# tfmsx.net
KiCad netlist of a schematic drawn in EAGLE
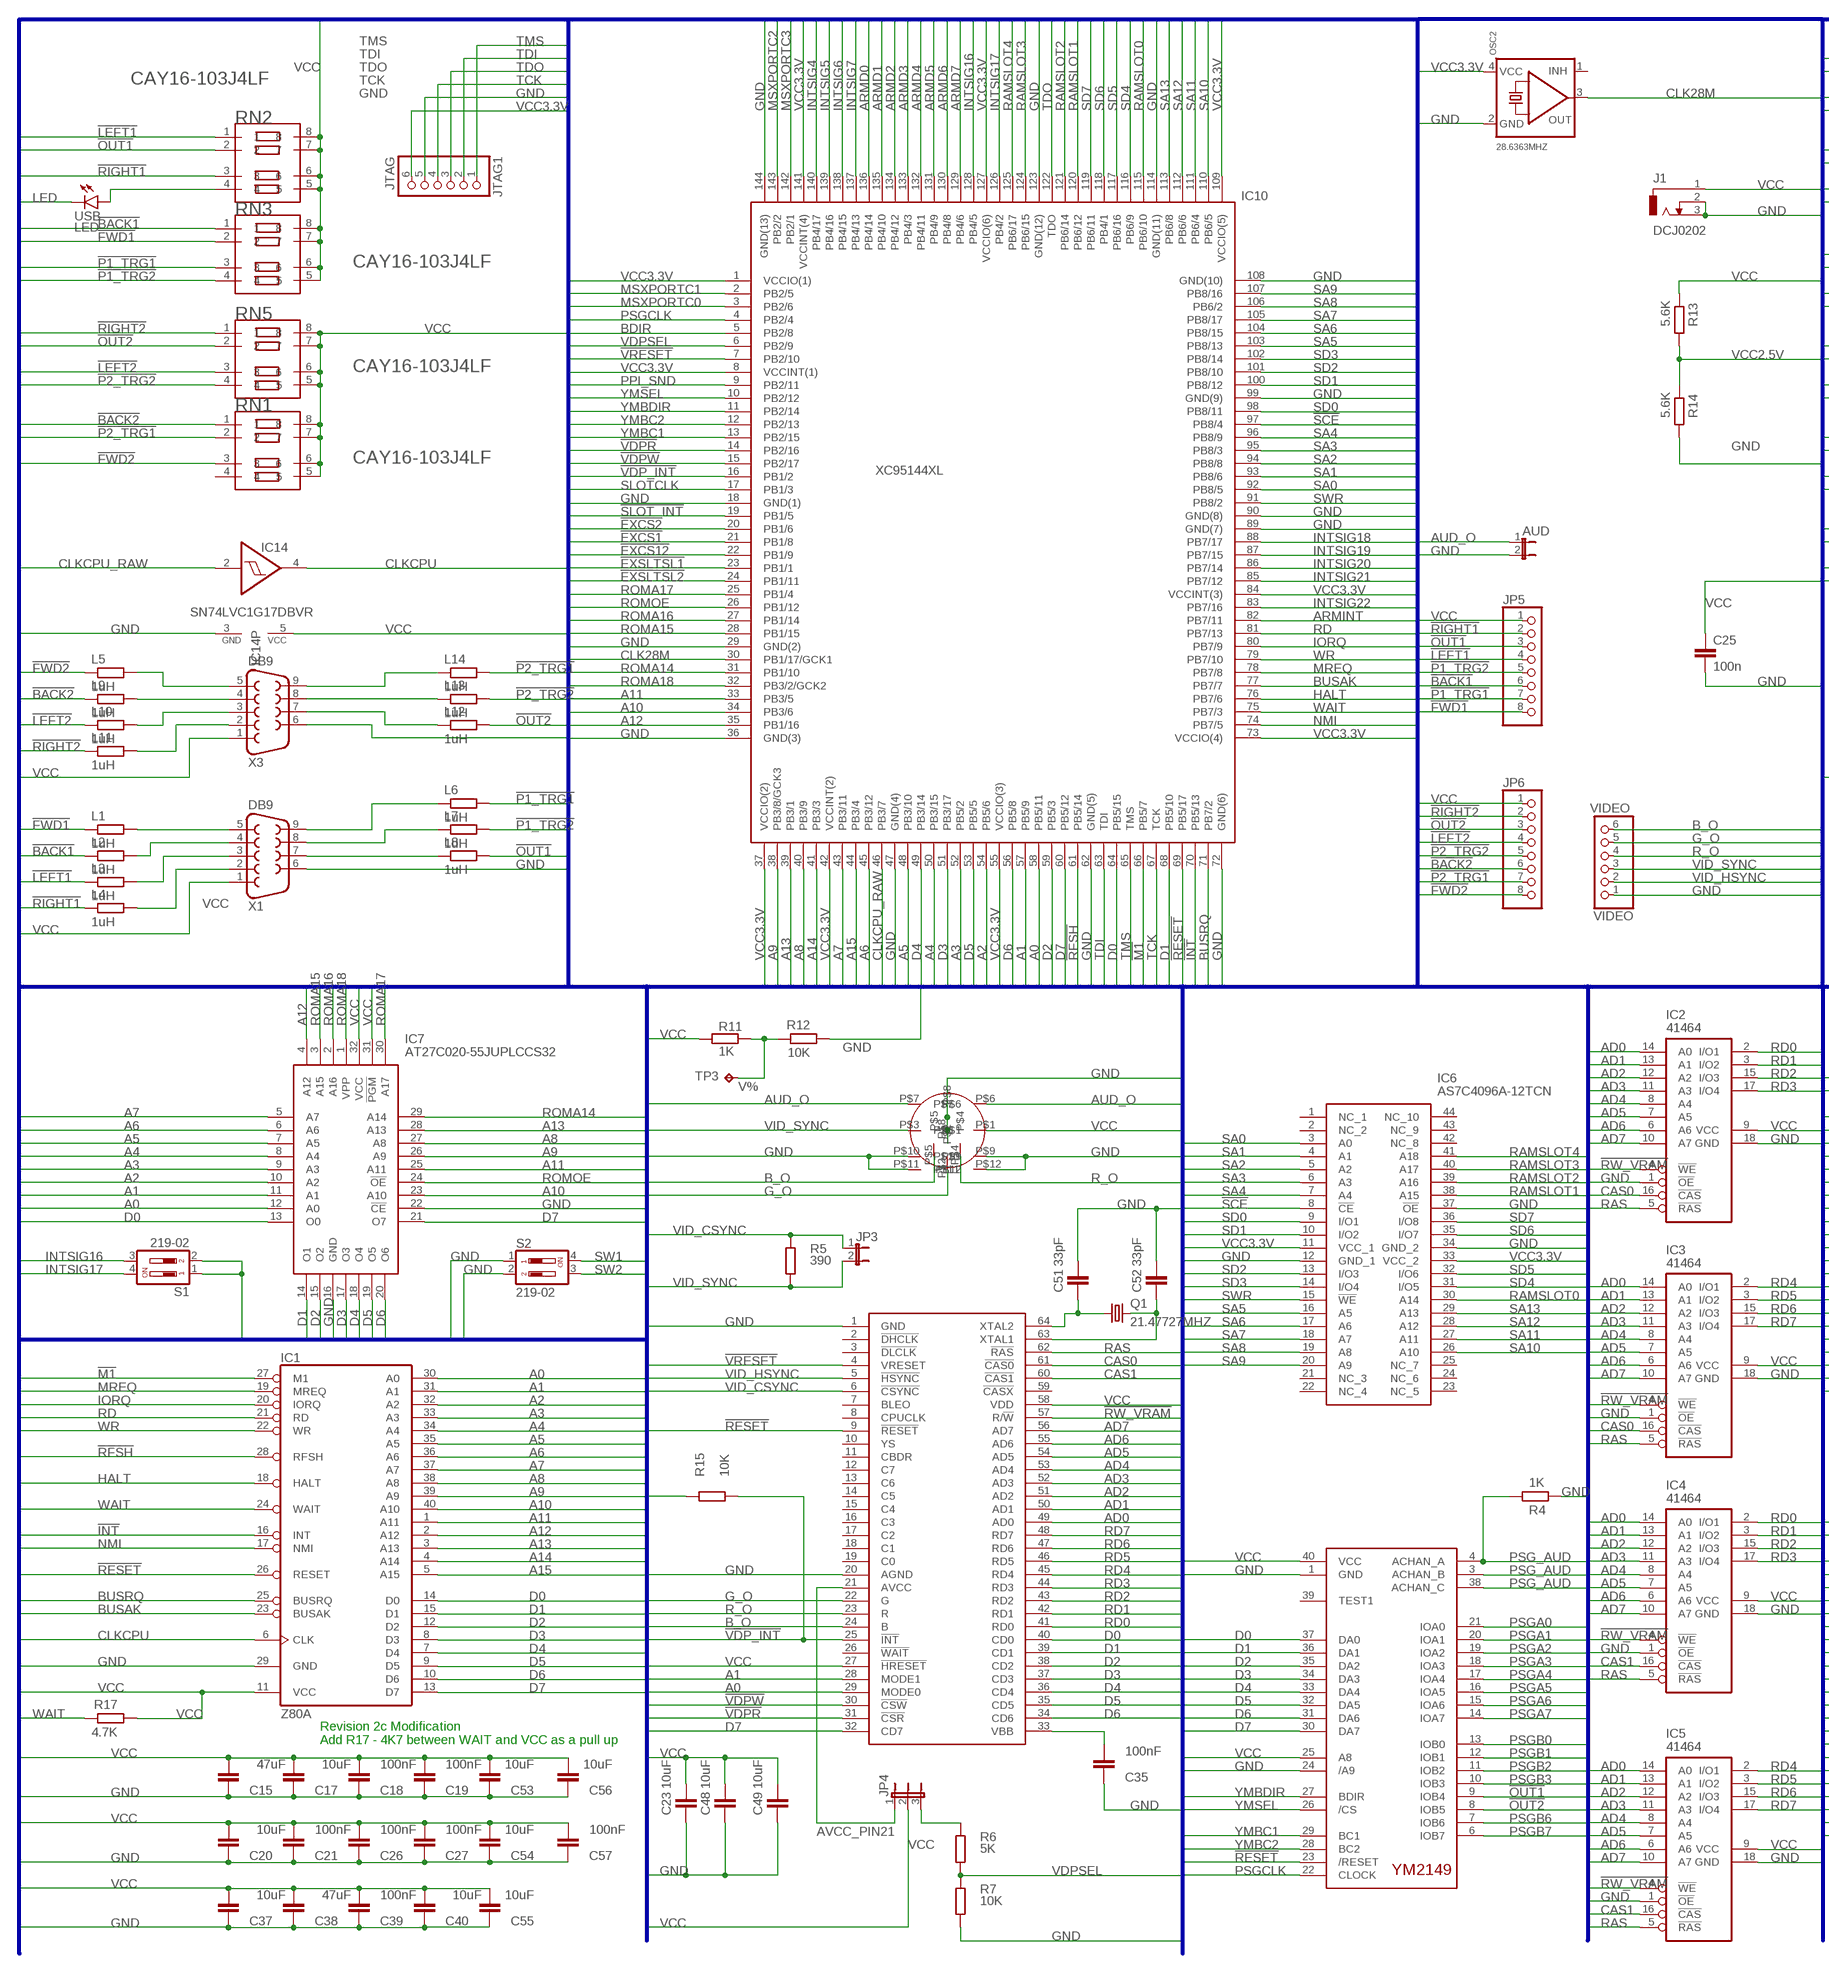
[diagram p0: schematic, sheet 1, part 1 of 2]
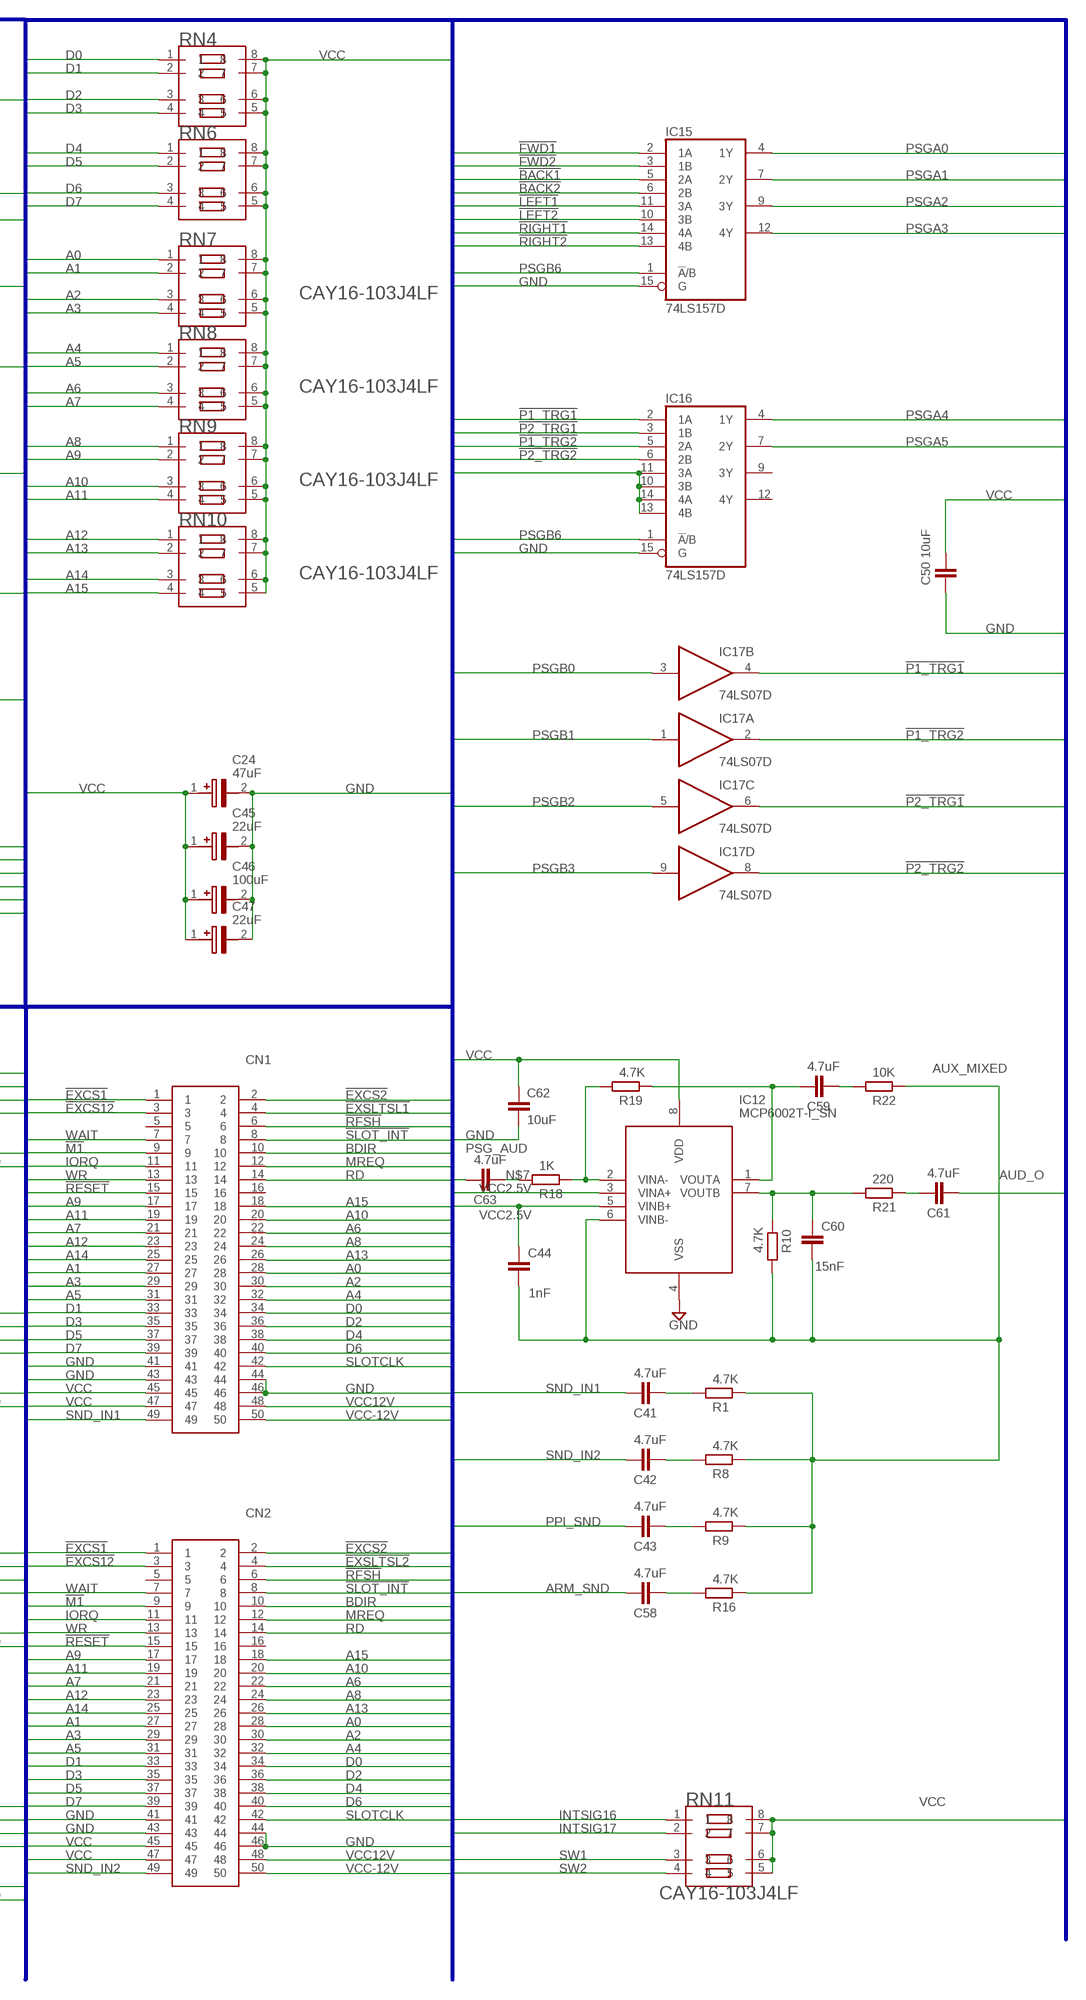
[diagram p1: schematic, sheet 1, part 2 of 2]
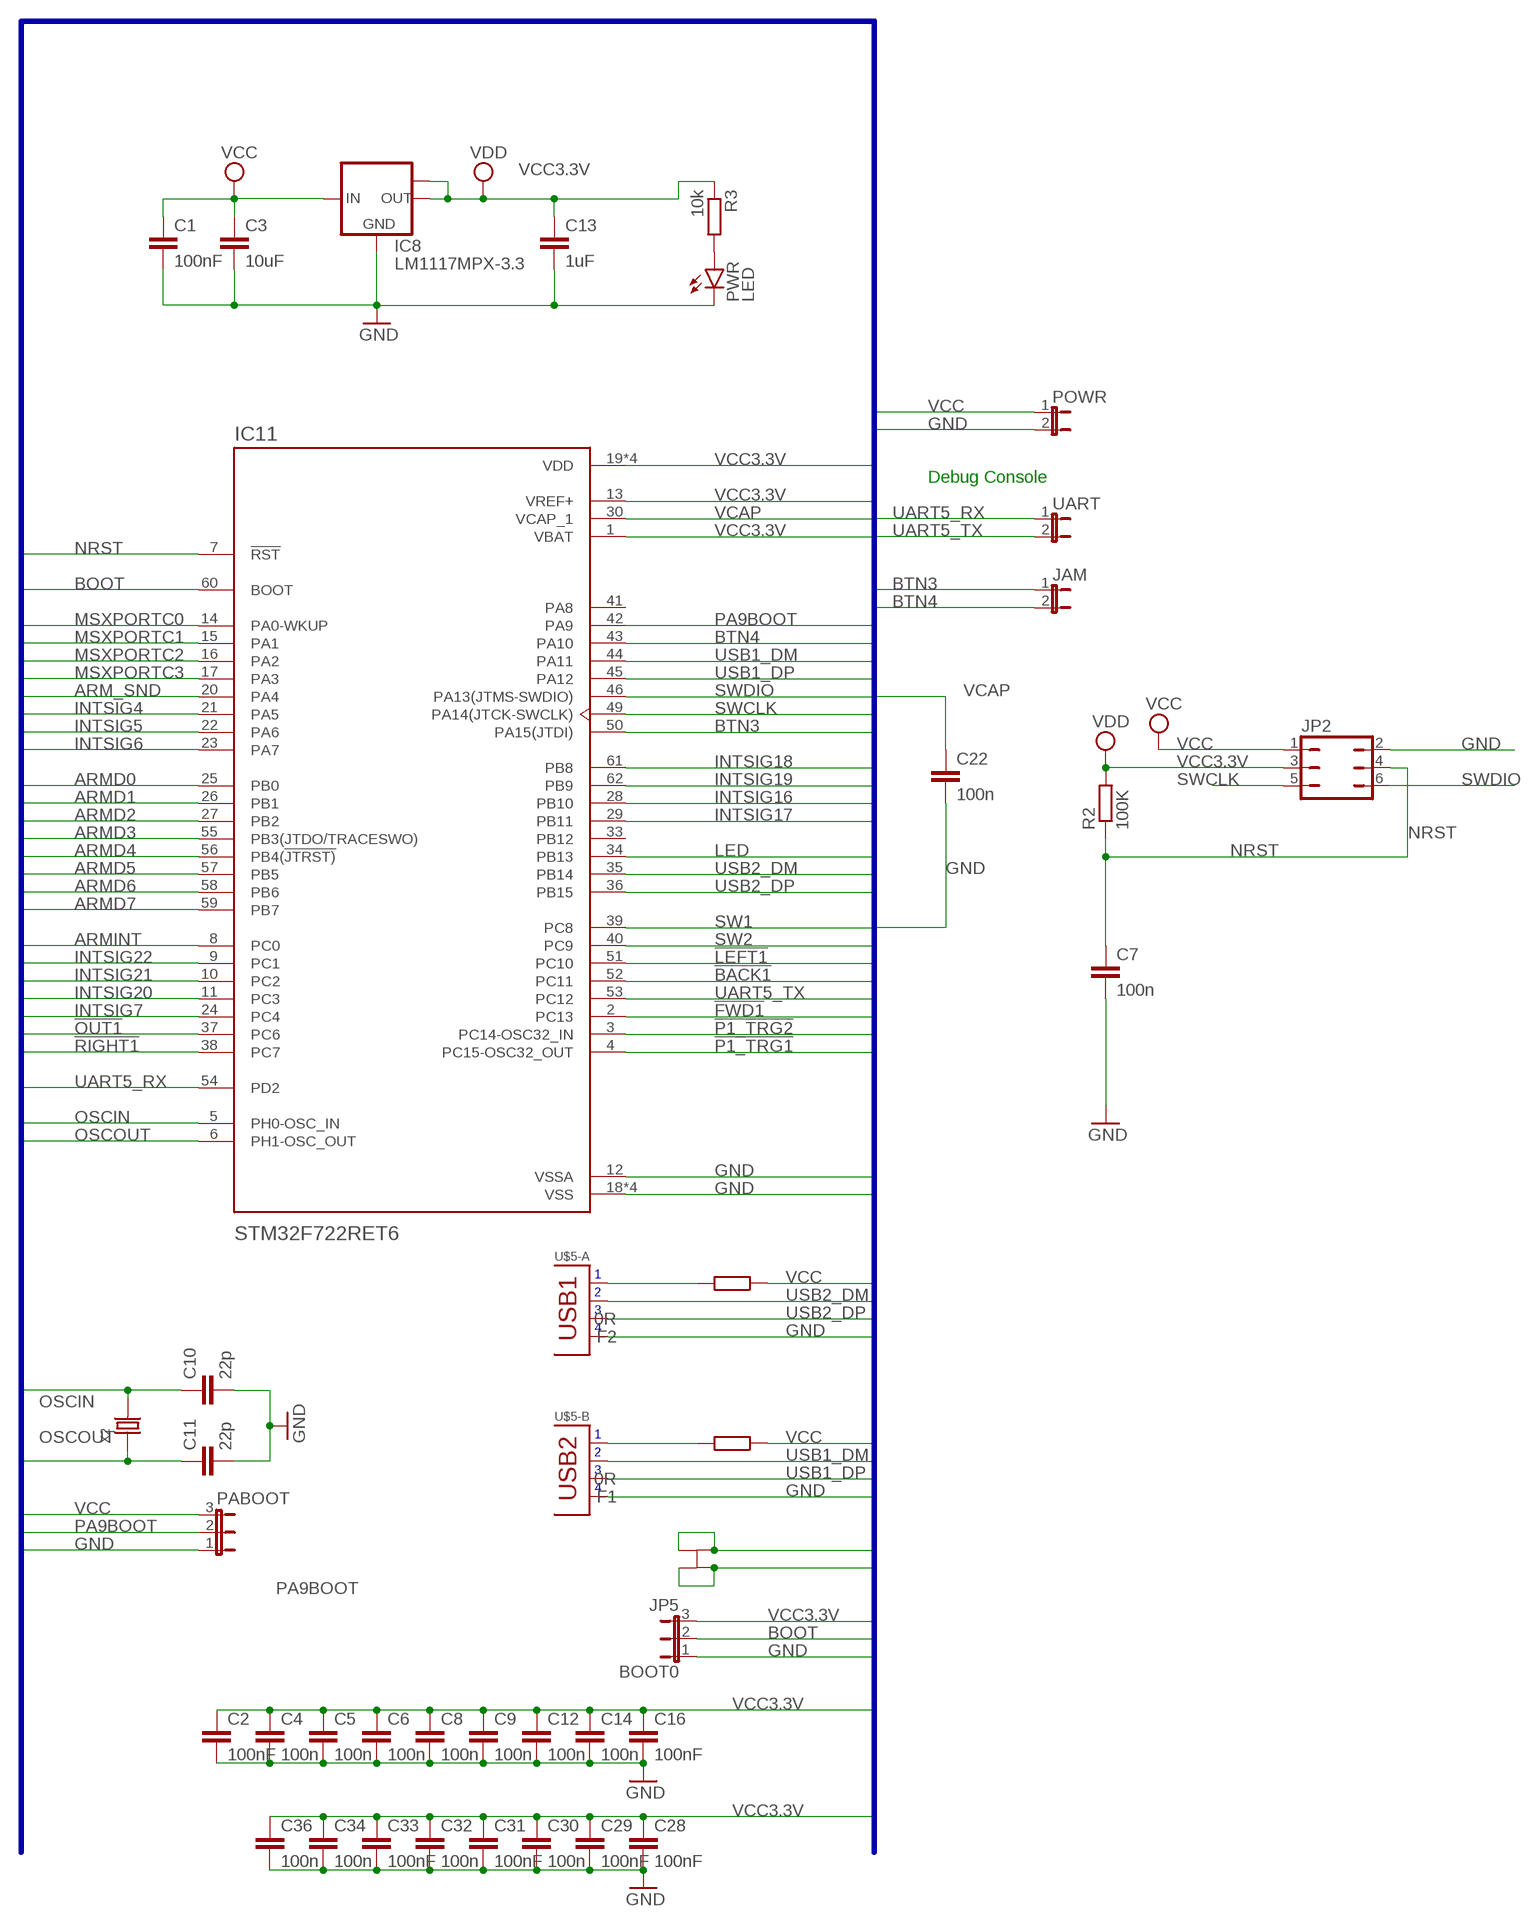
[diagram p2: schematic, sheet 2]

(export (version "E")
  (design (tool "Eeschema 10.0.6"))
  (components
    (comp (ref "AUD")
      (value "JUMPER-2PTH")
      (footprint "eagle-import:1X02")
      (libsource (lib "eagle-import") (part "JUMPER-2PTH"))
    )
    (comp (ref "C15")
      (value "47uF")
      (footprint "eagle-import:C1206")
      (libsource (lib "eagle-import") (part "C-EUC1206"))
    )
    (comp (ref "C17")
      (value "10uF")
      (footprint "eagle-import:C1206")
      (libsource (lib "eagle-import") (part "C-EUC1206"))
    )
    (comp (ref "C18")
      (value "100nF")
      (footprint "eagle-import:C1206")
      (libsource (lib "eagle-import") (part "C-EUC1206"))
    )
    (comp (ref "C19")
      (value "100nF")
      (footprint "eagle-import:C1206")
      (libsource (lib "eagle-import") (part "C-EUC1206"))
    )
    (comp (ref "C20")
      (value "10uF")
      (footprint "eagle-import:C1206")
      (libsource (lib "eagle-import") (part "C-EUC1206"))
    )
    (comp (ref "C21")
      (value "100nF")
      (footprint "eagle-import:C1206")
      (libsource (lib "eagle-import") (part "C-EUC1206"))
    )
    (comp (ref "C23")
      (value "10uF")
      (footprint "eagle-import:C1206")
      (libsource (lib "eagle-import") (part "C-EUC1206"))
    )
    (comp (ref "C24")
      (value "47uF")
      (footprint "eagle-import:CAPAE430X550N")
      (fields
        (field (name "MANUFACTURER_PART_NUMBER") "EEEHA1C100R")
        (field (name "RS_PART_NUMBER") "7472796P")
      )
      (libsource (lib "eagle-import") (part "EEEHA1C100R"))
    )
    (comp (ref "C25")
      (value "100n")
      (footprint "eagle-import:C0603")
      (libsource (lib "eagle-import") (part "C-EUC0603"))
    )
    (comp (ref "C26")
      (value "100nF")
      (footprint "eagle-import:C1206")
      (libsource (lib "eagle-import") (part "C-EUC1206"))
    )
    (comp (ref "C27")
      (value "100nF")
      (footprint "eagle-import:C1206")
      (libsource (lib "eagle-import") (part "C-EUC1206"))
    )
    (comp (ref "C35")
      (value "100nF")
      (footprint "eagle-import:C1206")
      (libsource (lib "eagle-import") (part "C-EUC1206"))
    )
    (comp (ref "C37")
      (value "10uF")
      (footprint "eagle-import:C1206")
      (libsource (lib "eagle-import") (part "C-EUC1206"))
    )
    (comp (ref "C38")
      (value "47uF")
      (footprint "eagle-import:C1206")
      (libsource (lib "eagle-import") (part "C-EUC1206"))
    )
    (comp (ref "C39")
      (value "100nF")
      (footprint "eagle-import:C1206")
      (libsource (lib "eagle-import") (part "C-EUC1206"))
    )
    (comp (ref "C40")
      (value "10uF")
      (footprint "eagle-import:C1206")
      (libsource (lib "eagle-import") (part "C-EUC1206"))
    )
    (comp (ref "C41")
      (value "4.7uF")
      (footprint "eagle-import:C0603")
      (libsource (lib "eagle-import") (part "C-EUC0603"))
    )
    (comp (ref "C42")
      (value "4.7uF")
      (footprint "eagle-import:C0603")
      (libsource (lib "eagle-import") (part "C-EUC0603"))
    )
    (comp (ref "C43")
      (value "4.7uF")
      (footprint "eagle-import:C0603")
      (libsource (lib "eagle-import") (part "C-EUC0603"))
    )
    (comp (ref "C44")
      (value "1nF")
      (footprint "eagle-import:C0603")
      (libsource (lib "eagle-import") (part "C-EUC0603"))
    )
    (comp (ref "C45")
      (value "22uF")
      (footprint "eagle-import:CAPAE430X550N")
      (fields
        (field (name "MANUFACTURER_PART_NUMBER") "EEEHA1C100R")
        (field (name "RS_PART_NUMBER") "7472796P")
      )
      (libsource (lib "eagle-import") (part "EEEHA1C100R"))
    )
    (comp (ref "C46")
      (value "100uF")
      (footprint "eagle-import:CAPAE430X550N")
      (fields
        (field (name "MANUFACTURER_PART_NUMBER") "EEEHA1C100R")
        (field (name "RS_PART_NUMBER") "7472796P")
      )
      (libsource (lib "eagle-import") (part "EEEHA1C100R"))
    )
    (comp (ref "C47")
      (value "22uF")
      (footprint "eagle-import:CAPAE430X550N")
      (fields
        (field (name "MANUFACTURER_PART_NUMBER") "EEEHA1C100R")
        (field (name "RS_PART_NUMBER") "7472796P")
      )
      (libsource (lib "eagle-import") (part "EEEHA1C100R"))
    )
    (comp (ref "C48")
      (value "10uF")
      (footprint "eagle-import:C1206")
      (libsource (lib "eagle-import") (part "C-EUC1206"))
    )
    (comp (ref "C49")
      (value "10uF")
      (footprint "eagle-import:C1206")
      (libsource (lib "eagle-import") (part "C-EUC1206"))
    )
    (comp (ref "C50")
      (value "10uF")
      (footprint "eagle-import:C1206")
      (libsource (lib "eagle-import") (part "C-EUC1206"))
    )
    (comp (ref "C51")
      (value "33pF")
      (footprint "eagle-import:C0805")
      (libsource (lib "eagle-import") (part "resistor_348_C-EUC0805"))
    )
    (comp (ref "C52")
      (value "33pF")
      (footprint "eagle-import:C0805")
      (libsource (lib "eagle-import") (part "resistor_348_C-EUC0805"))
    )
    (comp (ref "C53")
      (value "10uF")
      (footprint "eagle-import:C1206")
      (libsource (lib "eagle-import") (part "C-EUC1206"))
    )
    (comp (ref "C54")
      (value "10uF")
      (footprint "eagle-import:C1206")
      (libsource (lib "eagle-import") (part "C-EUC1206"))
    )
    (comp (ref "C55")
      (value "10uF")
      (footprint "eagle-import:C1206")
      (libsource (lib "eagle-import") (part "C-EUC1206"))
    )
    (comp (ref "C56")
      (value "10uF")
      (footprint "eagle-import:C1206")
      (libsource (lib "eagle-import") (part "C-EUC1206"))
    )
    (comp (ref "C57")
      (value "100nF")
      (footprint "eagle-import:C1206")
      (libsource (lib "eagle-import") (part "C-EUC1206"))
    )
    (comp (ref "C58")
      (value "4.7uF")
      (footprint "eagle-import:C0603")
      (libsource (lib "eagle-import") (part "C-EUC0603"))
    )
    (comp (ref "C59")
      (value "4.7uF")
      (footprint "eagle-import:C0603")
      (libsource (lib "eagle-import") (part "C-EUC0603"))
    )
    (comp (ref "C60")
      (value "15nF")
      (footprint "eagle-import:C0603")
      (libsource (lib "eagle-import") (part "C-EUC0603"))
    )
    (comp (ref "C61")
      (value "4.7uF")
      (footprint "eagle-import:C0603")
      (libsource (lib "eagle-import") (part "C-EUC0603"))
    )
    (comp (ref "C62")
      (value "10uF")
      (footprint "eagle-import:C1206")
      (libsource (lib "eagle-import") (part "C-EUC1206"))
    )
    (comp (ref "C63")
      (value "4.7uF")
      (footprint "eagle-import:C0603")
      (libsource (lib "eagle-import") (part "C-EUC0603"))
    )
    (comp (ref "CN1")
      (value "5530843-5")
      (footprint "eagle-import:55308435")
      (fields (field (name "MOUSER_PART_NUMBER") "571-5530843-5"))
      (libsource (lib "eagle-import") (part "5530843-5"))
    )
    (comp (ref "CN2")
      (value "5530843-5")
      (footprint "eagle-import:55308435")
      (fields (field (name "MOUSER_PART_NUMBER") "571-5530843-5"))
      (libsource (lib "eagle-import") (part "5530843-5"))
    )
    (comp (ref "IC1")
      (value "Z80A")
      (footprint "eagle-import:DIL40")
      (libsource (lib "eagle-import") (part "Z80CPU"))
    )
    (comp (ref "IC2")
      (value "41464")
      (footprint "eagle-import:DIL18")
      (libsource (lib "eagle-import") (part "41464"))
    )
    (comp (ref "IC3")
      (value "41464")
      (footprint "eagle-import:DIL18")
      (libsource (lib "eagle-import") (part "41464"))
    )
    (comp (ref "IC4")
      (value "41464")
      (footprint "eagle-import:DIL18")
      (libsource (lib "eagle-import") (part "41464"))
    )
    (comp (ref "IC5")
      (value "41464")
      (footprint "eagle-import:DIL18")
      (libsource (lib "eagle-import") (part "41464"))
    )
    (comp (ref "IC6")
      (value "AS7C4096A-12TCN")
      (footprint "eagle-import:SOP80P1181X120-44N")
      (fields (field (name "MOUSER_PART_NUMBER") "913-AS7C4096A-12TCN"))
      (libsource (lib "eagle-import") (part "AS7C4096A-12TCN"))
    )
    (comp (ref "IC7")
      (value "AT27C020-55JUPLCCS32")
      (footprint "eagle-import:PLCC-S32")
      (libsource (lib "eagle-import") (part "AT27C020-55JUPLCCS32"))
    )
    (comp (ref "IC9")
      (value "VDP9958")
      (footprint "eagle-import:SOT274")
      (libsource (lib "eagle-import") (part "VDP9958"))
    )
    (comp (ref "IC10")
      (value "XC95144XL")
      (footprint "eagle-import:SAMACSYS_PARTS_QFP50P2200X2200X160-144N")
      (fields
        (field (name "MANUFACTURER_PART_NUMBER") "XC95144XL-10TQG144I")
        (field (name "RS_PART_NUMBER") "6260624")
      )
      (libsource (lib "eagle-import") (part "SAMACSYS_PARTS_XC95144XL-10TQG144I"))
    )
    (comp (ref "IC12")
      (value "MCP6002T-I_SN")
      (footprint "eagle-import:SOIC127P600X175-8N")
      (fields
        (field (name "MANUFACTURER_PART_NUMBER") "MCP6002T-I/SN")
        (field (name "RS_PART_NUMBER") "8234276P")
      )
      (libsource (lib "eagle-import") (part "MCP6002T-I_SN"))
    )
    (comp (ref "IC13")
      (value "YM2149")
      (footprint "eagle-import:DIL40")
      (libsource (lib "eagle-import") (part "YM2149"))
    )
    (comp (ref "IC14")
      (value "SN74LVC1G17DBVR")
      (footprint "eagle-import:SOT23-5")
      (libsource (lib "eagle-import") (part "741G17DBVLVC"))
    )
    (comp (ref "IC15")
      (value "74LS157D")
      (footprint "eagle-import:SO16")
      (libsource (lib "eagle-import") (part "74157DLS"))
    )
    (comp (ref "IC16")
      (value "74LS157D")
      (footprint "eagle-import:SO16")
      (libsource (lib "eagle-import") (part "74157DLS"))
    )
    (comp (ref "IC17")
      (value "74LS07D")
      (footprint "eagle-import:SO14")
      (libsource (lib "eagle-import") (part "7407DLS"))
    )
    (comp (ref "J1")
      (value "DCJ0202")
      (footprint "eagle-import:DCJ0202")
      (libsource (lib "eagle-import") (part "DCJ0202"))
    )
    (comp (ref "JP3")
      (value "JP1E")
      (footprint "eagle-import:JP1")
      (libsource (lib "eagle-import") (part "JP1E"))
    )
    (comp (ref "JP4")
      (value "JP2E")
      (footprint "eagle-import:JP2")
      (libsource (lib "eagle-import") (part "JP2E"))
    )
    (comp (ref "JP5")
      (value "HEADER-1X8ROUND")
      (footprint "eagle-import:1X08_ROUND")
      (libsource (lib "eagle-import") (part "HEADER-1X8ROUND"))
    )
    (comp (ref "JP6")
      (value "HEADER-1X8ROUND")
      (footprint "eagle-import:1X08_ROUND")
      (libsource (lib "eagle-import") (part "HEADER-1X8ROUND"))
    )
    (comp (ref "JTAG1")
      (value "JTAG")
      (footprint "eagle-import:1X06_ROUND")
      (libsource (lib "eagle-import") (part "HEADER-1X6ROUND"))
    )
    (comp (ref "L1")
      (value "1uH")
      (footprint "eagle-import:R1206")
      (libsource (lib "eagle-import") (part "R-EU_R1206"))
    )
    (comp (ref "L2")
      (value "1uH")
      (footprint "eagle-import:R1206")
      (libsource (lib "eagle-import") (part "R-EU_R1206"))
    )
    (comp (ref "L3")
      (value "1uH")
      (footprint "eagle-import:R1206")
      (libsource (lib "eagle-import") (part "R-EU_R1206"))
    )
    (comp (ref "L4")
      (value "1uH")
      (footprint "eagle-import:R1206")
      (libsource (lib "eagle-import") (part "R-EU_R1206"))
    )
    (comp (ref "L5")
      (value "1uH")
      (footprint "eagle-import:R1206")
      (libsource (lib "eagle-import") (part "R-EU_R1206"))
    )
    (comp (ref "L6")
      (value "1uH")
      (footprint "eagle-import:R1206")
      (libsource (lib "eagle-import") (part "R-EU_R1206"))
    )
    (comp (ref "L7")
      (value "1uH")
      (footprint "eagle-import:R1206")
      (libsource (lib "eagle-import") (part "R-EU_R1206"))
    )
    (comp (ref "L8")
      (value "1uH")
      (footprint "eagle-import:R1206")
      (libsource (lib "eagle-import") (part "R-EU_R1206"))
    )
    (comp (ref "L9")
      (value "1uH")
      (footprint "eagle-import:R1206")
      (libsource (lib "eagle-import") (part "R-EU_R1206"))
    )
    (comp (ref "L10")
      (value "1uH")
      (footprint "eagle-import:R1206")
      (libsource (lib "eagle-import") (part "R-EU_R1206"))
    )
    (comp (ref "L11")
      (value "1uH")
      (footprint "eagle-import:R1206")
      (libsource (lib "eagle-import") (part "R-EU_R1206"))
    )
    (comp (ref "L12")
      (value "1uH")
      (footprint "eagle-import:R1206")
      (libsource (lib "eagle-import") (part "R-EU_R1206"))
    )
    (comp (ref "L13")
      (value "1uH")
      (footprint "eagle-import:R1206")
      (libsource (lib "eagle-import") (part "R-EU_R1206"))
    )
    (comp (ref "L14")
      (value "1uH")
      (footprint "eagle-import:R1206")
      (libsource (lib "eagle-import") (part "R-EU_R1206"))
    )
    (comp (ref "OSC2")
      (value "28.6363MHZ")
      (footprint "eagle-import:OSC_7X5MM")
      (libsource (lib "eagle-import") (part "OSCILLATOR"))
    )
    (comp (ref "Q1")
      (value "21.47727MHZ")
      (footprint "eagle-import:HC49_S")
      (libsource (lib "eagle-import") (part "CRYSTALHC49S"))
    )
    (comp (ref "R1")
      (value "4.7K")
      (footprint "eagle-import:M0805")
      (libsource (lib "eagle-import") (part "R-EU_M0805"))
    )
    (comp (ref "R4")
      (value "1K")
      (footprint "eagle-import:M0805")
      (libsource (lib "eagle-import") (part "R-EU_M0805"))
    )
    (comp (ref "R5")
      (value "390")
      (footprint "eagle-import:M0805")
      (libsource (lib "eagle-import") (part "R-EU_M0805"))
    )
    (comp (ref "R6")
      (value "5K")
      (footprint "eagle-import:M0805")
      (libsource (lib "eagle-import") (part "R-EU_M0805"))
    )
    (comp (ref "R7")
      (value "10K")
      (footprint "eagle-import:M0805")
      (libsource (lib "eagle-import") (part "R-EU_M0805"))
    )
    (comp (ref "R8")
      (value "4.7K")
      (footprint "eagle-import:M0805")
      (libsource (lib "eagle-import") (part "R-EU_M0805"))
    )
    (comp (ref "R9")
      (value "4.7K")
      (footprint "eagle-import:M0805")
      (libsource (lib "eagle-import") (part "R-EU_M0805"))
    )
    (comp (ref "R10")
      (value "4.7K")
      (footprint "eagle-import:M0805")
      (libsource (lib "eagle-import") (part "R-EU_M0805"))
    )
    (comp (ref "R11")
      (value "1K")
      (footprint "eagle-import:M0805")
      (libsource (lib "eagle-import") (part "R-EU_M0805"))
    )
    (comp (ref "R12")
      (value "10K")
      (footprint "eagle-import:M0805")
      (libsource (lib "eagle-import") (part "R-EU_M0805"))
    )
    (comp (ref "R13")
      (value "5.6K")
      (footprint "eagle-import:M0805")
      (libsource (lib "eagle-import") (part "R-EU_M0805"))
    )
    (comp (ref "R14")
      (value "5.6K")
      (footprint "eagle-import:M0805")
      (libsource (lib "eagle-import") (part "R-EU_M0805"))
    )
    (comp (ref "R15")
      (value "10K")
      (footprint "eagle-import:M0805")
      (libsource (lib "eagle-import") (part "R-EU_M0805"))
    )
    (comp (ref "R16")
      (value "4.7K")
      (footprint "eagle-import:M0805")
      (libsource (lib "eagle-import") (part "R-EU_M0805"))
    )
    (comp (ref "R17")
      (value "4.7K")
      (footprint "eagle-import:M0805")
      (libsource (lib "eagle-import") (part "R-EU_M0805"))
    )
    (comp (ref "R18")
      (value "1K")
      (footprint "eagle-import:M0805")
      (libsource (lib "eagle-import") (part "R-EU_M0805"))
    )
    (comp (ref "R19")
      (value "4.7K")
      (footprint "eagle-import:M0805")
      (libsource (lib "eagle-import") (part "R-EU_M0805"))
    )
    (comp (ref "R21")
      (value "220")
      (footprint "eagle-import:M0805")
      (libsource (lib "eagle-import") (part "R-EU_M0805"))
    )
    (comp (ref "R22")
      (value "10K")
      (footprint "eagle-import:M0805")
      (libsource (lib "eagle-import") (part "R-EU_M0805"))
    )
    (comp (ref "RN1")
      (value "CAY16-103J4LF")
      (footprint "eagle-import:RESCAXE80P320X160-8N")
      (fields (field (name "MF") "Bourns"))
      (libsource (lib "eagle-import") (part "CAY16-103J4LF"))
    )
    (comp (ref "RN2")
      (value "CAY16-103J4LF")
      (footprint "eagle-import:RESCAXE80P320X160-8N")
      (fields (field (name "MF") "Bourns"))
      (libsource (lib "eagle-import") (part "CAY16-103J4LF"))
    )
    (comp (ref "RN3")
      (value "CAY16-103J4LF")
      (footprint "eagle-import:RESCAXE80P320X160-8N")
      (fields (field (name "MF") "Bourns"))
      (libsource (lib "eagle-import") (part "CAY16-103J4LF"))
    )
    (comp (ref "RN4")
      (value "CAY16-103J4LF")
      (footprint "eagle-import:RESCAXE80P320X160-8N")
      (fields (field (name "MF") "Bourns"))
      (libsource (lib "eagle-import") (part "CAY16-103J4LF"))
    )
    (comp (ref "RN5")
      (value "CAY16-103J4LF")
      (footprint "eagle-import:RESCAXE80P320X160-8N")
      (fields (field (name "MF") "Bourns"))
      (libsource (lib "eagle-import") (part "CAY16-103J4LF"))
    )
    (comp (ref "RN6")
      (value "CAY16-103J4LF")
      (footprint "eagle-import:RESCAXE80P320X160-8N")
      (fields (field (name "MF") "Bourns"))
      (libsource (lib "eagle-import") (part "CAY16-103J4LF"))
    )
    (comp (ref "RN7")
      (value "CAY16-103J4LF")
      (footprint "eagle-import:RESCAXE80P320X160-8N")
      (fields (field (name "MF") "Bourns"))
      (libsource (lib "eagle-import") (part "CAY16-103J4LF"))
    )
    (comp (ref "RN8")
      (value "CAY16-103J4LF")
      (footprint "eagle-import:RESCAXE80P320X160-8N")
      (fields (field (name "MF") "Bourns"))
      (libsource (lib "eagle-import") (part "CAY16-103J4LF"))
    )
    (comp (ref "RN9")
      (value "CAY16-103J4LF")
      (footprint "eagle-import:RESCAXE80P320X160-8N")
      (fields (field (name "MF") "Bourns"))
      (libsource (lib "eagle-import") (part "CAY16-103J4LF"))
    )
    (comp (ref "RN10")
      (value "CAY16-103J4LF")
      (footprint "eagle-import:RESCAXE80P320X160-8N")
      (fields (field (name "MF") "Bourns"))
      (libsource (lib "eagle-import") (part "CAY16-103J4LF"))
    )
    (comp (ref "RN11")
      (value "CAY16-103J4LF")
      (footprint "eagle-import:RESCAXE80P320X160-8N")
      (fields (field (name "MF") "Bourns"))
      (libsource (lib "eagle-import") (part "CAY16-103J4LF"))
    )
    (comp (ref "S1")
      (value "219-02")
      (footprint "eagle-import:CTS-219-02")
      (libsource (lib "eagle-import") (part "219-02"))
    )
    (comp (ref "S2")
      (value "219-02")
      (footprint "eagle-import:CTS-219-02")
      (libsource (lib "eagle-import") (part "219-02"))
    )
    (comp (ref "TP3")
      (value "TPB1,27")
      (footprint "eagle-import:B1,27")
      (libsource (lib "eagle-import") (part "TPB1,27"))
    )
    (comp (ref "U$3")
      (value "DIN45326")
      (footprint "eagle-import:838_DIN8")
      (libsource (lib "eagle-import") (part "DIN45326"))
    )
    (comp (ref "USB")
      (value "LED")
      (footprint "eagle-import:SML0805")
      (libsource (lib "eagle-import") (part "LEDSML0805"))
    )
    (comp (ref "VIDEO")
      (value "VIDEO")
      (footprint "eagle-import:1X06_ROUND")
      (libsource (lib "eagle-import") (part "HEADER-1X6ROUND"))
    )
    (comp (ref "X1")
      (value "DB9")
      (footprint "eagle-import:F09HP")
      (libsource (lib "eagle-import") (part "F09HP"))
    )
    (comp (ref "X3")
      (value "DB9")
      (footprint "eagle-import:F09HP")
      (libsource (lib "eagle-import") (part "F09HP"))
    )
    (comp (ref "BOOT0")
      (value "JP5")
      (footprint "eagle-import:JP2")
      (libsource (lib "eagle-import") (part "JP2E"))
    )
    (comp (ref "C1")
      (value "100nF")
      (footprint "eagle-import:C1206")
      (libsource (lib "eagle-import") (part "C-EUC1206"))
    )
    (comp (ref "C2")
      (value "100nF")
      (footprint "eagle-import:C0603")
      (libsource (lib "eagle-import") (part "CC0603"))
    )
    (comp (ref "C3")
      (value "10uF")
      (footprint "eagle-import:C0603")
      (libsource (lib "eagle-import") (part "CC0603"))
    )
    (comp (ref "C4")
      (value "100n")
      (footprint "eagle-import:C0603")
      (libsource (lib "eagle-import") (part "CC0603"))
    )
    (comp (ref "C5")
      (value "100n")
      (footprint "eagle-import:C0603")
      (libsource (lib "eagle-import") (part "CC0603"))
    )
    (comp (ref "C6")
      (value "100n")
      (footprint "eagle-import:C0603")
      (libsource (lib "eagle-import") (part "C-EUC0603"))
    )
    (comp (ref "C7")
      (value "100n")
      (footprint "eagle-import:C0603")
      (libsource (lib "eagle-import") (part "CC0603"))
    )
    (comp (ref "C8")
      (value "100n")
      (footprint "eagle-import:C0603")
      (libsource (lib "eagle-import") (part "CC0603"))
    )
    (comp (ref "C9")
      (value "100n")
      (footprint "eagle-import:C0603")
      (libsource (lib "eagle-import") (part "CC0603"))
    )
    (comp (ref "C10")
      (value "22p")
      (footprint "eagle-import:C0603")
      (libsource (lib "eagle-import") (part "CC0603"))
    )
    (comp (ref "C11")
      (value "22p")
      (footprint "eagle-import:C0603")
      (libsource (lib "eagle-import") (part "CC0603"))
    )
    (comp (ref "C12")
      (value "100n")
      (footprint "eagle-import:C0603")
      (libsource (lib "eagle-import") (part "C-EUC0603"))
    )
    (comp (ref "C13")
      (value "1uF")
      (footprint "eagle-import:C1206")
      (libsource (lib "eagle-import") (part "C-EUC1206"))
    )
    (comp (ref "C14")
      (value "100n")
      (footprint "eagle-import:C0603")
      (libsource (lib "eagle-import") (part "CC0603"))
    )
    (comp (ref "C16")
      (value "100nF")
      (footprint "eagle-import:C0603")
      (libsource (lib "eagle-import") (part "CC0603"))
    )
    (comp (ref "C22")
      (value "100n")
      (footprint "eagle-import:C0805")
      (libsource (lib "eagle-import") (part "C-EUC0805"))
    )
    (comp (ref "C28")
      (value "100nF")
      (footprint "eagle-import:C0603")
      (libsource (lib "eagle-import") (part "CC0603"))
    )
    (comp (ref "C29")
      (value "100nF")
      (footprint "eagle-import:C0603")
      (libsource (lib "eagle-import") (part "CC0603"))
    )
    (comp (ref "C30")
      (value "100n")
      (footprint "eagle-import:C0603")
      (libsource (lib "eagle-import") (part "C-EUC0603"))
    )
    (comp (ref "C31")
      (value "100nF")
      (footprint "eagle-import:C0603")
      (libsource (lib "eagle-import") (part "CC0603"))
    )
    (comp (ref "C32")
      (value "100n")
      (footprint "eagle-import:C0603")
      (libsource (lib "eagle-import") (part "CC0603"))
    )
    (comp (ref "C33")
      (value "100nF")
      (footprint "eagle-import:C0603")
      (libsource (lib "eagle-import") (part "C-EUC0603"))
    )
    (comp (ref "C34")
      (value "100n")
      (footprint "eagle-import:C0603")
      (libsource (lib "eagle-import") (part "C-EUC0603"))
    )
    (comp (ref "C36")
      (value "100n")
      (footprint "eagle-import:C0603")
      (libsource (lib "eagle-import") (part "CC0603"))
    )
    (comp (ref "F1")
      (value "0R")
      (footprint "eagle-import:R1206")
      (libsource (lib "eagle-import") (part "RR1206"))
    )
    (comp (ref "F2")
      (value "0R")
      (footprint "eagle-import:R1206")
      (libsource (lib "eagle-import") (part "RR1206"))
    )
    (comp (ref "IC8")
      (value "LM1117MPX-3.3")
      (footprint "eagle-import:SOT223")
      (libsource (lib "eagle-import") (part "LM1117MPX-3.3"))
    )
    (comp (ref "IC11")
      (value "STM32F722RET6")
      (footprint "eagle-import:QFP50P1200X1200X160-64N")
      (fields (field (name "MF") "STMicroelectronics"))
      (libsource (lib "eagle-import") (part "STM32F722RET6"))
    )
    (comp (ref "JAM")
      (value "JUMPER-2PTH")
      (footprint "eagle-import:1X02")
      (libsource (lib "eagle-import") (part "JUMPER-2PTH"))
    )
    (comp (ref "JP2")
      (value "JP3Q")
      (footprint "eagle-import:JP3Q")
      (libsource (lib "eagle-import") (part "JP3Q"))
    )
    (comp (ref "PA9BOOT")
      (value "PABOOT")
      (footprint "eagle-import:JP2")
      (libsource (lib "eagle-import") (part "JP2E"))
    )
    (comp (ref "POWR")
      (value "JUMPER-2PTH")
      (footprint "eagle-import:1X02")
      (libsource (lib "eagle-import") (part "JUMPER-2PTH"))
    )
    (comp (ref "PWR")
      (value "LED")
      (footprint "eagle-import:SML0805")
      (libsource (lib "eagle-import") (part "LEDSML0805"))
    )
    (comp (ref "R2")
      (value "100K")
      (footprint "eagle-import:M0805")
      (libsource (lib "eagle-import") (part "R-EU_M0805"))
    )
    (comp (ref "R3")
      (value "10k")
      (footprint "eagle-import:R0603")
      (libsource (lib "eagle-import") (part "R-EU_R0603"))
    )
    (comp (ref "U$5")
      (value "USB-A-2_USB_USB-A-2")
      (footprint "eagle-import:USB-A-2_USB_USB-A-2")
      (libsource (lib "eagle-import") (part "USB-A-2_USB_USB-A-2"))
    )
    (comp (ref "UART")
      (value "JUMPER-2PTH")
      (footprint "eagle-import:1X02")
      (libsource (lib "eagle-import") (part "JUMPER-2PTH"))
    )
    (comp (ref "X2")
      (value "SMD-CRYSTAL-25MHZ-20PF-20PPM(2P-5.0X3.2MM)")
      (footprint "eagle-import:X2-SMD-5.0X3.2X1.3MM")
      (fields (field (name "MF") "Xinhunjing") (field (name "MP") "5032/4P"))
      (libsource (lib "eagle-import") (part "SMD-CRYSTAL-8MHZ-20PF-20PPM(2P-5.0X3.2MM)"))
    )
  )
  (nets
    (net (code "1") (name "A0") (class "Default")
      (node (ref "CN1") (pin "28") (pinfunction "28_28") (pintype "bidirectional"))
      (node (ref "CN2") (pin "28") (pinfunction "28_28") (pintype "bidirectional"))
      (node (ref "IC1") (pin "30") (pinfunction "A0_30") (pintype "output"))
      (node (ref "IC10") (pin "58") (pinfunction "PB5/11_58") (pintype "input"))
      (node (ref "IC7") (pin "12") (pinfunction "A0_12") (pintype "bidirectional"))
      (node (ref "IC9") (pin "29") (pinfunction "MODE0_29") (pintype "bidirectional"))
      (node (ref "RN7") (pin "1") (pinfunction "1_1") (pintype "passive"))
    )
    (net (code "2") (name "A1") (class "Default")
      (node (ref "CN1") (pin "27") (pinfunction "27_27") (pintype "bidirectional"))
      (node (ref "CN2") (pin "27") (pinfunction "27_27") (pintype "bidirectional"))
      (node (ref "IC1") (pin "31") (pinfunction "A1_31") (pintype "output"))
      (node (ref "IC10") (pin "57") (pinfunction "PB5/9_57") (pintype "input"))
      (node (ref "IC7") (pin "11") (pinfunction "A1_11") (pintype "bidirectional"))
      (node (ref "IC9") (pin "28") (pinfunction "MODE1_28") (pintype "bidirectional"))
      (node (ref "RN7") (pin "2") (pinfunction "2_2") (pintype "passive"))
    )
    (net (code "3") (name "A2") (class "Default")
      (node (ref "CN1") (pin "30") (pinfunction "30_30") (pintype "bidirectional"))
      (node (ref "CN2") (pin "30") (pinfunction "30_30") (pintype "bidirectional"))
      (node (ref "IC1") (pin "32") (pinfunction "A2_32") (pintype "output"))
      (node (ref "IC10") (pin "54") (pinfunction "PB5/6_54") (pintype "input"))
      (node (ref "IC7") (pin "10") (pinfunction "A2_10") (pintype "bidirectional"))
      (node (ref "RN7") (pin "3") (pinfunction "3_3") (pintype "passive"))
    )
    (net (code "4") (name "A3") (class "Default")
      (node (ref "CN1") (pin "29") (pinfunction "29_29") (pintype "bidirectional"))
      (node (ref "CN2") (pin "29") (pinfunction "29_29") (pintype "bidirectional"))
      (node (ref "IC1") (pin "33") (pinfunction "A3_33") (pintype "output"))
      (node (ref "IC10") (pin "52") (pinfunction "PB5/2_52") (pintype "input"))
      (node (ref "IC7") (pin "9") (pinfunction "A3_9") (pintype "bidirectional"))
      (node (ref "RN7") (pin "4") (pinfunction "4_4") (pintype "passive"))
    )
    (net (code "5") (name "A4") (class "Default")
      (node (ref "CN1") (pin "32") (pinfunction "32_32") (pintype "bidirectional"))
      (node (ref "CN2") (pin "32") (pinfunction "32_32") (pintype "bidirectional"))
      (node (ref "IC1") (pin "34") (pinfunction "A4_34") (pintype "output"))
      (node (ref "IC10") (pin "50") (pinfunction "PB3/15_50") (pintype "input"))
      (node (ref "IC7") (pin "8") (pinfunction "A4_8") (pintype "bidirectional"))
      (node (ref "RN8") (pin "1") (pinfunction "1_1") (pintype "passive"))
    )
    (net (code "6") (name "A5") (class "Default")
      (node (ref "CN1") (pin "31") (pinfunction "31_31") (pintype "bidirectional"))
      (node (ref "CN2") (pin "31") (pinfunction "31_31") (pintype "bidirectional"))
      (node (ref "IC1") (pin "35") (pinfunction "A5_35") (pintype "output"))
      (node (ref "IC10") (pin "48") (pinfunction "PB3/10_48") (pintype "input"))
      (node (ref "IC7") (pin "7") (pinfunction "A5_7") (pintype "bidirectional"))
      (node (ref "RN8") (pin "2") (pinfunction "2_2") (pintype "passive"))
    )
    (net (code "7") (name "A6") (class "Default")
      (node (ref "CN1") (pin "22") (pinfunction "22_22") (pintype "bidirectional"))
      (node (ref "CN2") (pin "22") (pinfunction "22_22") (pintype "bidirectional"))
      (node (ref "IC1") (pin "36") (pinfunction "A6_36") (pintype "output"))
      (node (ref "IC10") (pin "45") (pinfunction "PB3/12_45") (pintype "input"))
      (node (ref "IC7") (pin "6") (pinfunction "A6_6") (pintype "bidirectional"))
      (node (ref "RN8") (pin "3") (pinfunction "3_3") (pintype "passive"))
    )
    (net (code "8") (name "A7") (class "Default")
      (node (ref "CN1") (pin "21") (pinfunction "21_21") (pintype "bidirectional"))
      (node (ref "CN2") (pin "21") (pinfunction "21_21") (pintype "bidirectional"))
      (node (ref "IC1") (pin "37") (pinfunction "A7_37") (pintype "output"))
      (node (ref "IC10") (pin "43") (pinfunction "PB3/11_43") (pintype "input"))
      (node (ref "IC7") (pin "5") (pinfunction "A7_5") (pintype "bidirectional"))
      (node (ref "RN8") (pin "4") (pinfunction "4_4") (pintype "passive"))
    )
    (net (code "9") (name "A8") (class "Default")
      (node (ref "CN1") (pin "24") (pinfunction "24_24") (pintype "bidirectional"))
      (node (ref "CN2") (pin "24") (pinfunction "24_24") (pintype "bidirectional"))
      (node (ref "IC1") (pin "38") (pinfunction "A8_38") (pintype "output"))
      (node (ref "IC10") (pin "40") (pinfunction "PB3/9_40") (pintype "input"))
      (node (ref "IC7") (pin "27") (pinfunction "A8_27") (pintype "bidirectional"))
      (node (ref "RN9") (pin "1") (pinfunction "1_1") (pintype "passive"))
    )
    (net (code "10") (name "A9") (class "Default")
      (node (ref "CN1") (pin "17") (pinfunction "17_17") (pintype "bidirectional"))
      (node (ref "CN2") (pin "17") (pinfunction "17_17") (pintype "bidirectional"))
      (node (ref "IC1") (pin "39") (pinfunction "A9_39") (pintype "output"))
      (node (ref "IC10") (pin "38") (pinfunction "PB3/8/GCK3_38") (pintype "input"))
      (node (ref "IC7") (pin "26") (pinfunction "A9_26") (pintype "bidirectional"))
      (node (ref "RN9") (pin "2") (pinfunction "2_2") (pintype "passive"))
    )
    (net (code "11") (name "A10") (class "Default")
      (node (ref "CN1") (pin "20") (pinfunction "20_20") (pintype "bidirectional"))
      (node (ref "CN2") (pin "20") (pinfunction "20_20") (pintype "bidirectional"))
      (node (ref "IC1") (pin "40") (pinfunction "A10_40") (pintype "output"))
      (node (ref "IC10") (pin "34") (pinfunction "PB3/6_34") (pintype "input"))
      (node (ref "IC7") (pin "23") (pinfunction "A10_23") (pintype "bidirectional"))
      (node (ref "RN9") (pin "3") (pinfunction "3_3") (pintype "passive"))
    )
    (net (code "12") (name "A11") (class "Default")
      (node (ref "CN1") (pin "19") (pinfunction "19_19") (pintype "bidirectional"))
      (node (ref "CN2") (pin "19") (pinfunction "19_19") (pintype "bidirectional"))
      (node (ref "IC1") (pin "1") (pinfunction "A11_1") (pintype "output"))
      (node (ref "IC10") (pin "33") (pinfunction "PB3/5_33") (pintype "input"))
      (node (ref "IC7") (pin "25") (pinfunction "A11_25") (pintype "bidirectional"))
      (node (ref "RN9") (pin "4") (pinfunction "4_4") (pintype "passive"))
    )
    (net (code "13") (name "A12") (class "Default")
      (node (ref "CN1") (pin "23") (pinfunction "23_23") (pintype "bidirectional"))
      (node (ref "CN2") (pin "23") (pinfunction "23_23") (pintype "bidirectional"))
      (node (ref "IC1") (pin "2") (pinfunction "A12_2") (pintype "output"))
      (node (ref "IC10") (pin "35") (pinfunction "PB1/16_35") (pintype "input"))
      (node (ref "IC7") (pin "4") (pinfunction "A12_4") (pintype "bidirectional"))
      (node (ref "RN10") (pin "1") (pinfunction "1_1") (pintype "passive"))
    )
    (net (code "14") (name "A13") (class "Default")
      (node (ref "CN1") (pin "26") (pinfunction "26_26") (pintype "bidirectional"))
      (node (ref "CN2") (pin "26") (pinfunction "26_26") (pintype "bidirectional"))
      (node (ref "IC1") (pin "3") (pinfunction "A13_3") (pintype "output"))
      (node (ref "IC10") (pin "39") (pinfunction "PB3/1_39") (pintype "input"))
      (node (ref "IC7") (pin "28") (pinfunction "A13_28") (pintype "bidirectional"))
      (node (ref "RN10") (pin "2") (pinfunction "2_2") (pintype "passive"))
    )
    (net (code "15") (name "A14") (class "Default")
      (node (ref "CN1") (pin "25") (pinfunction "25_25") (pintype "bidirectional"))
      (node (ref "CN2") (pin "25") (pinfunction "25_25") (pintype "bidirectional"))
      (node (ref "IC1") (pin "4") (pinfunction "A14_4") (pintype "output"))
      (node (ref "IC10") (pin "41") (pinfunction "PB3/3_41") (pintype "input"))
      (node (ref "RN10") (pin "3") (pinfunction "3_3") (pintype "passive"))
    )
    (net (code "16") (name "A15") (class "Default")
      (node (ref "CN1") (pin "18") (pinfunction "18_18") (pintype "bidirectional"))
      (node (ref "CN2") (pin "18") (pinfunction "18_18") (pintype "bidirectional"))
      (node (ref "IC1") (pin "5") (pinfunction "A15_5") (pintype "output"))
      (node (ref "IC10") (pin "44") (pinfunction "PB3/4_44") (pintype "input"))
      (node (ref "RN10") (pin "4") (pinfunction "4_4") (pintype "passive"))
    )
    (net (code "17") (name "AD0") (class "Default")
      (node (ref "IC2") (pin "14") (pinfunction "A0_14") (pintype "input"))
      (node (ref "IC3") (pin "14") (pinfunction "A0_14") (pintype "input"))
      (node (ref "IC4") (pin "14") (pinfunction "A0_14") (pintype "input"))
      (node (ref "IC5") (pin "14") (pinfunction "A0_14") (pintype "input"))
      (node (ref "IC9") (pin "49") (pinfunction "AD0_49") (pintype "bidirectional"))
    )
    (net (code "18") (name "AD1") (class "Default")
      (node (ref "IC2") (pin "13") (pinfunction "A1_13") (pintype "input"))
      (node (ref "IC3") (pin "13") (pinfunction "A1_13") (pintype "input"))
      (node (ref "IC4") (pin "13") (pinfunction "A1_13") (pintype "input"))
      (node (ref "IC5") (pin "13") (pinfunction "A1_13") (pintype "input"))
      (node (ref "IC9") (pin "50") (pinfunction "AD1_50") (pintype "bidirectional"))
    )
    (net (code "19") (name "AD2") (class "Default")
      (node (ref "IC2") (pin "12") (pinfunction "A2_12") (pintype "input"))
      (node (ref "IC3") (pin "12") (pinfunction "A2_12") (pintype "input"))
      (node (ref "IC4") (pin "12") (pinfunction "A2_12") (pintype "input"))
      (node (ref "IC5") (pin "12") (pinfunction "A2_12") (pintype "input"))
      (node (ref "IC9") (pin "51") (pinfunction "AD2_51") (pintype "bidirectional"))
    )
    (net (code "20") (name "AD3") (class "Default")
      (node (ref "IC2") (pin "11") (pinfunction "A3_11") (pintype "input"))
      (node (ref "IC3") (pin "11") (pinfunction "A3_11") (pintype "input"))
      (node (ref "IC4") (pin "11") (pinfunction "A3_11") (pintype "input"))
      (node (ref "IC5") (pin "11") (pinfunction "A3_11") (pintype "input"))
      (node (ref "IC9") (pin "52") (pinfunction "AD3_52") (pintype "bidirectional"))
    )
    (net (code "21") (name "AD4") (class "Default")
      (node (ref "IC2") (pin "8") (pinfunction "A4_8") (pintype "input"))
      (node (ref "IC3") (pin "8") (pinfunction "A4_8") (pintype "input"))
      (node (ref "IC4") (pin "8") (pinfunction "A4_8") (pintype "input"))
      (node (ref "IC5") (pin "8") (pinfunction "A4_8") (pintype "input"))
      (node (ref "IC9") (pin "53") (pinfunction "AD4_53") (pintype "bidirectional"))
    )
    (net (code "22") (name "AD5") (class "Default")
      (node (ref "IC2") (pin "7") (pinfunction "A5_7") (pintype "input"))
      (node (ref "IC3") (pin "7") (pinfunction "A5_7") (pintype "input"))
      (node (ref "IC4") (pin "7") (pinfunction "A5_7") (pintype "input"))
      (node (ref "IC5") (pin "7") (pinfunction "A5_7") (pintype "input"))
      (node (ref "IC9") (pin "54") (pinfunction "AD5_54") (pintype "bidirectional"))
    )
    (net (code "23") (name "AD6") (class "Default")
      (node (ref "IC2") (pin "6") (pinfunction "A6_6") (pintype "input"))
      (node (ref "IC3") (pin "6") (pinfunction "A6_6") (pintype "input"))
      (node (ref "IC4") (pin "6") (pinfunction "A6_6") (pintype "input"))
      (node (ref "IC5") (pin "6") (pinfunction "A6_6") (pintype "input"))
      (node (ref "IC9") (pin "55") (pinfunction "AD6_55") (pintype "bidirectional"))
    )
    (net (code "24") (name "AD7") (class "Default")
      (node (ref "IC2") (pin "10") (pinfunction "A7_10") (pintype "input"))
      (node (ref "IC3") (pin "10") (pinfunction "A7_10") (pintype "input"))
      (node (ref "IC4") (pin "10") (pinfunction "A7_10") (pintype "input"))
      (node (ref "IC5") (pin "10") (pinfunction "A7_10") (pintype "input"))
      (node (ref "IC9") (pin "56") (pinfunction "AD7_56") (pintype "bidirectional"))
    )
    (net (code "25") (name "ARMD0") (class "Default")
      (node (ref "IC10") (pin "136") (pinfunction "PB4/14_136") (pintype "input"))
      (node (ref "IC11") (pin "25") (pinfunction "PB0_25") (pintype "bidirectional"))
    )
    (net (code "26") (name "ARMD1") (class "Default")
      (node (ref "IC10") (pin "135") (pinfunction "PB4/10_135") (pintype "input"))
      (node (ref "IC11") (pin "26") (pinfunction "PB1_26") (pintype "bidirectional"))
    )
    (net (code "27") (name "ARMD2") (class "Default")
      (node (ref "IC10") (pin "134") (pinfunction "PB4/12_134") (pintype "input"))
      (node (ref "IC11") (pin "27") (pinfunction "PB2_27") (pintype "bidirectional"))
    )
    (net (code "28") (name "ARMD3") (class "Default")
      (node (ref "IC10") (pin "133") (pinfunction "PB4/3_133") (pintype "input"))
      (node (ref "IC11") (pin "55") (pinfunction "PB3(JTDO/TRACESWO)_55") (pintype "bidirectional"))
    )
    (net (code "29") (name "ARMD4") (class "Default")
      (node (ref "IC10") (pin "132") (pinfunction "PB4/11_132") (pintype "input"))
      (node (ref "IC11") (pin "56") (pinfunction "PB4(~{JTRST})_56") (pintype "bidirectional"))
    )
    (net (code "30") (name "ARMD5") (class "Default")
      (node (ref "IC10") (pin "131") (pinfunction "PB4/9_131") (pintype "input"))
      (node (ref "IC11") (pin "57") (pinfunction "PB5_57") (pintype "bidirectional"))
    )
    (net (code "31") (name "ARMD6") (class "Default")
      (node (ref "IC10") (pin "130") (pinfunction "PB4/8_130") (pintype "input"))
      (node (ref "IC11") (pin "58") (pinfunction "PB6_58") (pintype "bidirectional"))
    )
    (net (code "32") (name "ARMD7") (class "Default")
      (node (ref "IC10") (pin "129") (pinfunction "PB4/6_129") (pintype "input"))
      (node (ref "IC11") (pin "59") (pinfunction "PB7_59") (pintype "bidirectional"))
    )
    (net (code "33") (name "ARMINT") (class "Default")
      (node (ref "IC10") (pin "82") (pinfunction "PB7/11_82") (pintype "input"))
      (node (ref "IC11") (pin "8") (pinfunction "PC0_8") (pintype "bidirectional"))
    )
    (net (code "34") (name "ARM_SND") (class "Default")
      (node (ref "C58") (pin "1") (pinfunction "1_1") (pintype "passive"))
      (node (ref "IC11") (pin "20") (pinfunction "PA4_20") (pintype "bidirectional"))
    )
    (net (code "35") (name "AUD_O") (class "Default")
      (node (ref "AUD") (pin "1") (pinfunction "1_1") (pintype "passive"))
      (node (ref "C61") (pin "2") (pinfunction "2_2") (pintype "passive"))
      (node (ref "U$3") (pin "P$6") (pinfunction "P$6_P$6") (pintype "bidirectional"))
      (node (ref "U$3") (pin "P$7") (pinfunction "P$7_P$7") (pintype "bidirectional"))
    )
    (net (code "36") (name "AUX_MIXED") (class "Default")
      (node (ref "C44") (pin "1") (pinfunction "1_1") (pintype "passive"))
      (node (ref "C60") (pin "1") (pinfunction "1_1") (pintype "passive"))
      (node (ref "IC12") (pin "6") (pinfunction "VINB-_6") (pintype "bidirectional"))
      (node (ref "R1") (pin "1") (pinfunction "1_1") (pintype "passive"))
      (node (ref "R10") (pin "2") (pinfunction "2_2") (pintype "passive"))
      (node (ref "R16") (pin "1") (pinfunction "1_1") (pintype "passive"))
      (node (ref "R22") (pin "1") (pinfunction "1_1") (pintype "passive"))
      (node (ref "R8") (pin "1") (pinfunction "1_1") (pintype "passive"))
      (node (ref "R9") (pin "1") (pinfunction "1_1") (pintype "passive"))
    )
    (net (code "37") (name "AVCC_PIN21") (class "Default")
      (node (ref "IC9") (pin "21") (pinfunction "AVCC_21") (pintype "bidirectional"))
      (node (ref "JP4") (pin "1") (pinfunction "1_1") (pintype "passive"))
    )
    (net (code "38") (name "BDIR") (class "Default")
      (node (ref "CN1") (pin "10") (pinfunction "10_10") (pintype "bidirectional"))
      (node (ref "CN2") (pin "10") (pinfunction "10_10") (pintype "bidirectional"))
      (node (ref "IC10") (pin "5") (pinfunction "PB2/8_5") (pintype "input"))
    )
    (net (code "39") (name "BOOT") (class "Default")
      (node (ref "BOOT0") (pin "2") (pinfunction "2_2") (pintype "passive"))
      (node (ref "IC11") (pin "60") (pinfunction "BOOT_60") (pintype "bidirectional"))
    )
    (net (code "40") (name "BTN3") (class "Default")
      (node (ref "IC11") (pin "50") (pinfunction "PA15(JTDI)_50") (pintype "bidirectional"))
      (node (ref "JAM") (pin "1") (pinfunction "1_1") (pintype "passive"))
    )
    (net (code "41") (name "BTN4") (class "Default")
      (node (ref "IC11") (pin "43") (pinfunction "PA10_43") (pintype "bidirectional"))
      (node (ref "JAM") (pin "2") (pinfunction "2_2") (pintype "passive"))
    )
    (net (code "42") (name "BUSAK") (class "Default")
      (node (ref "IC1") (pin "23") (pinfunction "BUSAK_23") (pintype "output"))
      (node (ref "IC10") (pin "77") (pinfunction "PB7/7_77") (pintype "input"))
    )
    (net (code "43") (name "BUSRQ") (class "Default")
      (node (ref "IC1") (pin "25") (pinfunction "BUSRQ_25") (pintype "input"))
      (node (ref "IC10") (pin "71") (pinfunction "PB7/2_71") (pintype "input"))
    )
    (net (code "44") (name "B_O") (class "Default")
      (node (ref "IC9") (pin "24") (pinfunction "B_24") (pintype "bidirectional"))
      (node (ref "U$3") (pin "P$5") (pinfunction "P$5_P$5") (pintype "bidirectional"))
      (node (ref "VIDEO") (pin "6") (pinfunction "6_6") (pintype "passive"))
    )
    (net (code "45") (name "CAS0") (class "Default")
      (node (ref "IC2") (pin "16") (pinfunction "~{CAS}_16") (pintype "input"))
      (node (ref "IC3") (pin "16") (pinfunction "~{CAS}_16") (pintype "input"))
      (node (ref "IC9") (pin "61") (pinfunction "~{CAS0}_61") (pintype "bidirectional"))
    )
    (net (code "46") (name "CAS1") (class "Default")
      (node (ref "IC4") (pin "16") (pinfunction "~{CAS}_16") (pintype "input"))
      (node (ref "IC5") (pin "16") (pinfunction "~{CAS}_16") (pintype "input"))
      (node (ref "IC9") (pin "60") (pinfunction "~{CAS1}_60") (pintype "bidirectional"))
    )
    (net (code "47") (name "CLK28M") (class "Default")
      (node (ref "IC10") (pin "30") (pinfunction "PB1/17/GCK1_30") (pintype "input"))
      (node (ref "OSC2") (pin "3") (pinfunction "OUT_3") (pintype "output"))
    )
    (net (code "48") (name "CLKCPU") (class "Default")
      (node (ref "IC1") (pin "6") (pinfunction "CLK_6") (pintype "input"))
      (node (ref "IC14") (pin "4") (pinfunction "O_4") (pintype "output"))
    )
    (net (code "49") (name "CLKCPU_RAW") (class "Default")
      (node (ref "IC10") (pin "46") (pinfunction "PB3/7_46") (pintype "input"))
      (node (ref "IC14") (pin "2") (pinfunction "I_2") (pintype "input"))
    )
    (net (code "50") (name "D0") (class "Default")
      (node (ref "CN1") (pin "34") (pinfunction "34_34") (pintype "bidirectional"))
      (node (ref "CN2") (pin "34") (pinfunction "34_34") (pintype "bidirectional"))
      (node (ref "IC1") (pin "14") (pinfunction "D0_14") (pintype "bidirectional"))
      (node (ref "IC10") (pin "64") (pinfunction "PB5/15_64") (pintype "input"))
      (node (ref "IC13") (pin "37") (pinfunction "DA0_37") (pintype "bidirectional"))
      (node (ref "IC7") (pin "13") (pinfunction "O0_13") (pintype "bidirectional"))
      (node (ref "IC9") (pin "40") (pinfunction "CD0_40") (pintype "bidirectional"))
      (node (ref "RN4") (pin "1") (pinfunction "1_1") (pintype "passive"))
    )
    (net (code "51") (name "D1") (class "Default")
      (node (ref "CN1") (pin "33") (pinfunction "33_33") (pintype "bidirectional"))
      (node (ref "CN2") (pin "33") (pinfunction "33_33") (pintype "bidirectional"))
      (node (ref "IC1") (pin "15") (pinfunction "D1_15") (pintype "bidirectional"))
      (node (ref "IC10") (pin "68") (pinfunction "PB5/10_68") (pintype "input"))
      (node (ref "IC13") (pin "36") (pinfunction "DA1_36") (pintype "bidirectional"))
      (node (ref "IC7") (pin "14") (pinfunction "O1_14") (pintype "bidirectional"))
      (node (ref "IC9") (pin "39") (pinfunction "CD1_39") (pintype "bidirectional"))
      (node (ref "RN4") (pin "2") (pinfunction "2_2") (pintype "passive"))
    )
    (net (code "52") (name "D2") (class "Default")
      (node (ref "CN1") (pin "36") (pinfunction "36_36") (pintype "bidirectional"))
      (node (ref "CN2") (pin "36") (pinfunction "36_36") (pintype "bidirectional"))
      (node (ref "IC1") (pin "12") (pinfunction "D2_12") (pintype "bidirectional"))
      (node (ref "IC10") (pin "59") (pinfunction "PB5/3_59") (pintype "input"))
      (node (ref "IC13") (pin "35") (pinfunction "DA2_35") (pintype "bidirectional"))
      (node (ref "IC7") (pin "15") (pinfunction "O2_15") (pintype "bidirectional"))
      (node (ref "IC9") (pin "38") (pinfunction "CD2_38") (pintype "bidirectional"))
      (node (ref "RN4") (pin "3") (pinfunction "3_3") (pintype "passive"))
    )
    (net (code "53") (name "D3") (class "Default")
      (node (ref "CN1") (pin "35") (pinfunction "35_35") (pintype "bidirectional"))
      (node (ref "CN2") (pin "35") (pinfunction "35_35") (pintype "bidirectional"))
      (node (ref "IC1") (pin "8") (pinfunction "D3_8") (pintype "bidirectional"))
      (node (ref "IC10") (pin "51") (pinfunction "PB3/17_51") (pintype "input"))
      (node (ref "IC13") (pin "34") (pinfunction "DA3_34") (pintype "bidirectional"))
      (node (ref "IC7") (pin "17") (pinfunction "O3_17") (pintype "bidirectional"))
      (node (ref "IC9") (pin "37") (pinfunction "CD3_37") (pintype "bidirectional"))
      (node (ref "RN4") (pin "4") (pinfunction "4_4") (pintype "passive"))
    )
    (net (code "54") (name "D4") (class "Default")
      (node (ref "CN1") (pin "38") (pinfunction "38_38") (pintype "bidirectional"))
      (node (ref "CN2") (pin "38") (pinfunction "38_38") (pintype "bidirectional"))
      (node (ref "IC1") (pin "7") (pinfunction "D4_7") (pintype "bidirectional"))
      (node (ref "IC10") (pin "49") (pinfunction "PB3/14_49") (pintype "input"))
      (node (ref "IC13") (pin "33") (pinfunction "DA4_33") (pintype "bidirectional"))
      (node (ref "IC7") (pin "18") (pinfunction "O4_18") (pintype "bidirectional"))
      (node (ref "IC9") (pin "36") (pinfunction "CD4_36") (pintype "bidirectional"))
      (node (ref "RN6") (pin "1") (pinfunction "1_1") (pintype "passive"))
    )
    (net (code "55") (name "D5") (class "Default")
      (node (ref "CN1") (pin "37") (pinfunction "37_37") (pintype "bidirectional"))
      (node (ref "CN2") (pin "37") (pinfunction "37_37") (pintype "bidirectional"))
      (node (ref "IC1") (pin "9") (pinfunction "D5_9") (pintype "bidirectional"))
      (node (ref "IC10") (pin "53") (pinfunction "PB5/5_53") (pintype "input"))
      (node (ref "IC13") (pin "32") (pinfunction "DA5_32") (pintype "bidirectional"))
      (node (ref "IC7") (pin "19") (pinfunction "O5_19") (pintype "bidirectional"))
      (node (ref "IC9") (pin "35") (pinfunction "CD5_35") (pintype "bidirectional"))
      (node (ref "RN6") (pin "2") (pinfunction "2_2") (pintype "passive"))
    )
    (net (code "56") (name "D6") (class "Default")
      (node (ref "CN1") (pin "40") (pinfunction "40_40") (pintype "bidirectional"))
      (node (ref "CN2") (pin "40") (pinfunction "40_40") (pintype "bidirectional"))
      (node (ref "IC1") (pin "10") (pinfunction "D6_10") (pintype "bidirectional"))
      (node (ref "IC10") (pin "56") (pinfunction "PB5/8_56") (pintype "input"))
      (node (ref "IC13") (pin "31") (pinfunction "DA6_31") (pintype "bidirectional"))
      (node (ref "IC7") (pin "20") (pinfunction "O6_20") (pintype "bidirectional"))
      (node (ref "IC9") (pin "34") (pinfunction "CD6_34") (pintype "bidirectional"))
      (node (ref "RN6") (pin "3") (pinfunction "3_3") (pintype "passive"))
    )
    (net (code "57") (name "D7") (class "Default")
      (node (ref "CN1") (pin "39") (pinfunction "39_39") (pintype "bidirectional"))
      (node (ref "CN2") (pin "39") (pinfunction "39_39") (pintype "bidirectional"))
      (node (ref "IC1") (pin "13") (pinfunction "D7_13") (pintype "bidirectional"))
      (node (ref "IC10") (pin "60") (pinfunction "PB5/12_60") (pintype "input"))
      (node (ref "IC13") (pin "30") (pinfunction "DA7_30") (pintype "bidirectional"))
      (node (ref "IC7") (pin "21") (pinfunction "O7_21") (pintype "bidirectional"))
      (node (ref "IC9") (pin "32") (pinfunction "CD7_32") (pintype "bidirectional"))
      (node (ref "RN6") (pin "4") (pinfunction "4_4") (pintype "passive"))
    )
    (net (code "58") (name "GND") (class "Default")
      (node (ref "AUD") (pin "2") (pinfunction "2_2") (pintype "passive"))
      (node (ref "BOOT0") (pin "1") (pinfunction "1_1") (pintype "passive"))
      (node (ref "C1") (pin "2") (pinfunction "2_2") (pintype "passive"))
      (node (ref "C10") (pin "2") (pinfunction "2_2") (pintype "passive"))
      (node (ref "C11") (pin "2") (pinfunction "2_2") (pintype "passive"))
      (node (ref "C12") (pin "2") (pinfunction "2_2") (pintype "passive"))
      (node (ref "C13") (pin "2") (pinfunction "2_2") (pintype "passive"))
      (node (ref "C14") (pin "2") (pinfunction "2_2") (pintype "passive"))
      (node (ref "C15") (pin "1") (pinfunction "1_1") (pintype "passive"))
      (node (ref "C16") (pin "2") (pinfunction "2_2") (pintype "passive"))
      (node (ref "C17") (pin "1") (pinfunction "1_1") (pintype "passive"))
      (node (ref "C18") (pin "1") (pinfunction "1_1") (pintype "passive"))
      (node (ref "C19") (pin "1") (pinfunction "1_1") (pintype "passive"))
      (node (ref "C2") (pin "2") (pinfunction "2_2") (pintype "passive"))
      (node (ref "C20") (pin "1") (pinfunction "1_1") (pintype "passive"))
      (node (ref "C21") (pin "1") (pinfunction "1_1") (pintype "passive"))
      (node (ref "C22") (pin "2") (pinfunction "2_2") (pintype "passive"))
      (node (ref "C23") (pin "1") (pinfunction "1_1") (pintype "passive"))
      (node (ref "C24") (pin "2") (pinfunction "-_2") (pintype "bidirectional"))
      (node (ref "C25") (pin "2") (pinfunction "2_2") (pintype "passive"))
      (node (ref "C26") (pin "1") (pinfunction "1_1") (pintype "passive"))
      (node (ref "C27") (pin "1") (pinfunction "1_1") (pintype "passive"))
      (node (ref "C28") (pin "2") (pinfunction "2_2") (pintype "passive"))
      (node (ref "C29") (pin "2") (pinfunction "2_2") (pintype "passive"))
      (node (ref "C3") (pin "2") (pinfunction "2_2") (pintype "passive"))
      (node (ref "C30") (pin "2") (pinfunction "2_2") (pintype "passive"))
      (node (ref "C31") (pin "2") (pinfunction "2_2") (pintype "passive"))
      (node (ref "C32") (pin "2") (pinfunction "2_2") (pintype "passive"))
      (node (ref "C33") (pin "2") (pinfunction "2_2") (pintype "passive"))
      (node (ref "C34") (pin "2") (pinfunction "2_2") (pintype "passive"))
      (node (ref "C35") (pin "1") (pinfunction "1_1") (pintype "passive"))
      (node (ref "C36") (pin "2") (pinfunction "2_2") (pintype "passive"))
      (node (ref "C37") (pin "1") (pinfunction "1_1") (pintype "passive"))
      (node (ref "C38") (pin "1") (pinfunction "1_1") (pintype "passive"))
      (node (ref "C39") (pin "1") (pinfunction "1_1") (pintype "passive"))
      (node (ref "C4") (pin "2") (pinfunction "2_2") (pintype "passive"))
      (node (ref "C40") (pin "1") (pinfunction "1_1") (pintype "passive"))
      (node (ref "C45") (pin "2") (pinfunction "-_2") (pintype "bidirectional"))
      (node (ref "C46") (pin "2") (pinfunction "-_2") (pintype "bidirectional"))
      (node (ref "C47") (pin "2") (pinfunction "-_2") (pintype "bidirectional"))
      (node (ref "C48") (pin "1") (pinfunction "1_1") (pintype "passive"))
      (node (ref "C49") (pin "1") (pinfunction "1_1") (pintype "passive"))
      (node (ref "C5") (pin "2") (pinfunction "2_2") (pintype "passive"))
      (node (ref "C50") (pin "1") (pinfunction "1_1") (pintype "passive"))
      (node (ref "C51") (pin "2") (pinfunction "2_2") (pintype "passive"))
      (node (ref "C52") (pin "2") (pinfunction "2_2") (pintype "passive"))
      (node (ref "C53") (pin "1") (pinfunction "1_1") (pintype "passive"))
      (node (ref "C54") (pin "1") (pinfunction "1_1") (pintype "passive"))
      (node (ref "C55") (pin "1") (pinfunction "1_1") (pintype "passive"))
      (node (ref "C56") (pin "1") (pinfunction "1_1") (pintype "passive"))
      (node (ref "C57") (pin "1") (pinfunction "1_1") (pintype "passive"))
      (node (ref "C6") (pin "2") (pinfunction "2_2") (pintype "passive"))
      (node (ref "C62") (pin "2") (pinfunction "2_2") (pintype "passive"))
      (node (ref "C7") (pin "2") (pinfunction "2_2") (pintype "passive"))
      (node (ref "C8") (pin "2") (pinfunction "2_2") (pintype "passive"))
      (node (ref "C9") (pin "2") (pinfunction "2_2") (pintype "passive"))
      (node (ref "CN1") (pin "41") (pinfunction "41_41") (pintype "bidirectional"))
      (node (ref "CN1") (pin "43") (pinfunction "43_43") (pintype "bidirectional"))
      (node (ref "CN1") (pin "44") (pinfunction "44_44") (pintype "bidirectional"))
      (node (ref "CN1") (pin "46") (pinfunction "46_46") (pintype "bidirectional"))
      (node (ref "CN2") (pin "41") (pinfunction "41_41") (pintype "bidirectional"))
      (node (ref "CN2") (pin "43") (pinfunction "43_43") (pintype "bidirectional"))
      (node (ref "CN2") (pin "44") (pinfunction "44_44") (pintype "bidirectional"))
      (node (ref "CN2") (pin "46") (pinfunction "46_46") (pintype "bidirectional"))
      (node (ref "IC1") (pin "29") (pinfunction "GND_29") (pintype "power_in"))
      (node (ref "IC10") (pin "108") (pinfunction "GND(10)_108") (pintype "input"))
      (node (ref "IC10") (pin "114") (pinfunction "GND(11)_114") (pintype "input"))
      (node (ref "IC10") (pin "123") (pinfunction "GND(12)_123") (pintype "input"))
      (node (ref "IC10") (pin "144") (pinfunction "GND(13)_144") (pintype "input"))
      (node (ref "IC10") (pin "18") (pinfunction "GND(1)_18") (pintype "input"))
      (node (ref "IC10") (pin "29") (pinfunction "GND(2)_29") (pintype "input"))
      (node (ref "IC10") (pin "36") (pinfunction "GND(3)_36") (pintype "input"))
      (node (ref "IC10") (pin "47") (pinfunction "GND(4)_47") (pintype "input"))
      (node (ref "IC10") (pin "62") (pinfunction "GND(5)_62") (pintype "input"))
      (node (ref "IC10") (pin "72") (pinfunction "GND(6)_72") (pintype "input"))
      (node (ref "IC10") (pin "89") (pinfunction "GND(7)_89") (pintype "input"))
      (node (ref "IC10") (pin "90") (pinfunction "GND(8)_90") (pintype "input"))
      (node (ref "IC10") (pin "99") (pinfunction "GND(9)_99") (pintype "input"))
      (node (ref "IC11") (pin "12") (pinfunction "VSSA_12") (pintype "power_in"))
      (node (ref "IC11") (pin "18") (pinfunction "VSS_18") (pintype "power_in"))
      (node (ref "IC11") (pin "31") (pinfunction "VSS_31") (pintype "power_in"))
      (node (ref "IC11") (pin "47") (pinfunction "VSS_47") (pintype "power_in"))
      (node (ref "IC11") (pin "63") (pinfunction "VSS_63") (pintype "power_in"))
      (node (ref "IC12") (pin "4") (pinfunction "VSS_4") (pintype "bidirectional"))
      (node (ref "IC13") (pin "1") (pinfunction "GND_1") (pintype "bidirectional"))
      (node (ref "IC13") (pin "24") (pinfunction "/A9_24") (pintype "bidirectional"))
      (node (ref "IC14") (pin "3") (pinfunction "GND_3") (pintype "power_in"))
      (node (ref "IC15") (pin "15") (pinfunction "G_15") (pintype "input"))
      (node (ref "IC16") (pin "10") (pinfunction "3B_10") (pintype "input"))
      (node (ref "IC16") (pin "11") (pinfunction "3A_11") (pintype "input"))
      (node (ref "IC16") (pin "13") (pinfunction "4B_13") (pintype "input"))
      (node (ref "IC16") (pin "14") (pinfunction "4A_14") (pintype "input"))
      (node (ref "IC16") (pin "15") (pinfunction "G_15") (pintype "input"))
      (node (ref "IC2") (pin "1") (pinfunction "~{OE}_1") (pintype "input"))
      (node (ref "IC2") (pin "18") (pinfunction "GND_18") (pintype "power_in"))
      (node (ref "IC3") (pin "1") (pinfunction "~{OE}_1") (pintype "input"))
      (node (ref "IC3") (pin "18") (pinfunction "GND_18") (pintype "power_in"))
      (node (ref "IC4") (pin "1") (pinfunction "~{OE}_1") (pintype "input"))
      (node (ref "IC4") (pin "18") (pinfunction "GND_18") (pintype "power_in"))
      (node (ref "IC5") (pin "1") (pinfunction "~{OE}_1") (pintype "input"))
      (node (ref "IC5") (pin "18") (pinfunction "GND_18") (pintype "power_in"))
      (node (ref "IC6") (pin "12") (pinfunction "GND_1_12") (pintype "bidirectional"))
      (node (ref "IC6") (pin "34") (pinfunction "GND_2_34") (pintype "bidirectional"))
      (node (ref "IC6") (pin "37") (pinfunction "~{OE}_37") (pintype "bidirectional"))
      (node (ref "IC7") (pin "16") (pinfunction "GND_16") (pintype "bidirectional"))
      (node (ref "IC7") (pin "22") (pinfunction "~{CE}_22") (pintype "bidirectional"))
      (node (ref "IC8") (pin "1") (pinfunction "GND_1") (pintype "input"))
      (node (ref "IC9") (pin "1") (pinfunction "GND_1") (pintype "power_in"))
      (node (ref "IC9") (pin "20") (pinfunction "AGND_20") (pintype "bidirectional"))
      (node (ref "J1") (pin "2") (pinfunction "2_2") (pintype "passive"))
      (node (ref "J1") (pin "3") (pinfunction "3_3") (pintype "passive"))
      (node (ref "JP2") (pin "2") (pinfunction "2_2") (pintype "passive"))
      (node (ref "JTAG1") (pin "5") (pinfunction "5_5") (pintype "passive"))
      (node (ref "OSC2") (pin "2") (pinfunction "GND_2") (pintype "power_in"))
      (node (ref "PA9BOOT") (pin "1") (pinfunction "1_1") (pintype "passive"))
      (node (ref "POWR") (pin "2") (pinfunction "2_2") (pintype "passive"))
      (node (ref "PWR") (pin "C") (pinfunction "C_C") (pintype "passive"))
      (node (ref "R12") (pin "1") (pinfunction "1_1") (pintype "passive"))
      (node (ref "R14") (pin "2") (pinfunction "2_2") (pintype "passive"))
      (node (ref "R4") (pin "1") (pinfunction "1_1") (pintype "passive"))
      (node (ref "R7") (pin "1") (pinfunction "1_1") (pintype "passive"))
      (node (ref "S1") (pin "1") (pinfunction "1_1") (pintype "passive"))
      (node (ref "S1") (pin "2") (pinfunction "2_2") (pintype "passive"))
      (node (ref "S2") (pin "1") (pinfunction "1_1") (pintype "passive"))
      (node (ref "S2") (pin "2") (pinfunction "2_2") (pintype "passive"))
      (node (ref "U$3") (pin "P$10") (pinfunction "P$10_P$10") (pintype "power_in"))
      (node (ref "U$3") (pin "P$11") (pinfunction "P$11_P$11") (pintype "power_in"))
      (node (ref "U$3") (pin "P$12") (pinfunction "P$12_P$12") (pintype "power_in"))
      (node (ref "U$3") (pin "P$8") (pinfunction "P$8_P$8") (pintype "bidirectional"))
      (node (ref "U$3") (pin "P$9") (pinfunction "P$9_P$9") (pintype "power_in"))
      (node (ref "U$5") (pin "1-4") (pinfunction "1-4_1-4") (pintype "bidirectional"))
      (node (ref "U$5") (pin "2-4") (pinfunction "2-4_2-4") (pintype "bidirectional"))
      (node (ref "U$5") (pin "SHIELD1") (pinfunction "SHIELD1_SHIELD1") (pintype "bidirectional"))
      (node (ref "U$5") (pin "SHIELD2") (pinfunction "SHIELD2_SHIELD2") (pintype "bidirectional"))
      (node (ref "U$5") (pin "SHIELD3") (pinfunction "SHIELD3_SHIELD3") (pintype "bidirectional"))
      (node (ref "U$5") (pin "SHIELD4") (pinfunction "SHIELD4_SHIELD4") (pintype "bidirectional"))
      (node (ref "VIDEO") (pin "1") (pinfunction "1_1") (pintype "passive"))
      (node (ref "X1") (pin "6") (pinfunction "6_6") (pintype "passive"))
      (node (ref "X3") (pin "6") (pinfunction "6_6") (pintype "passive"))
    )
    (net (code "59") (name "G_O") (class "Default")
      (node (ref "IC9") (pin "22") (pinfunction "G_22") (pintype "bidirectional"))
      (node (ref "U$3") (pin "P$2") (pinfunction "P$2_P$2") (pintype "bidirectional"))
      (node (ref "VIDEO") (pin "5") (pinfunction "5_5") (pintype "passive"))
    )
    (net (code "60") (name "HALT") (class "Default")
      (node (ref "IC1") (pin "18") (pinfunction "HALT_18") (pintype "output"))
      (node (ref "IC10") (pin "76") (pinfunction "PB7/6_76") (pintype "input"))
    )
    (net (code "61") (name "INTSIG4") (class "Default")
      (node (ref "IC10") (pin "140") (pinfunction "PB4/17_140") (pintype "input"))
      (node (ref "IC11") (pin "21") (pinfunction "PA5_21") (pintype "bidirectional"))
    )
    (net (code "62") (name "INTSIG5") (class "Default")
      (node (ref "IC10") (pin "139") (pinfunction "PB4/16_139") (pintype "input"))
      (node (ref "IC11") (pin "22") (pinfunction "PA6_22") (pintype "bidirectional"))
    )
    (net (code "63") (name "INTSIG6") (class "Default")
      (node (ref "IC10") (pin "138") (pinfunction "PB4/15_138") (pintype "input"))
      (node (ref "IC11") (pin "23") (pinfunction "PA7_23") (pintype "bidirectional"))
    )
    (net (code "64") (name "INTSIG7") (class "Default")
      (node (ref "IC10") (pin "137") (pinfunction "PB4/13_137") (pintype "input"))
      (node (ref "IC11") (pin "24") (pinfunction "PC4_24") (pintype "bidirectional"))
    )
    (net (code "65") (name "INTSIG16") (class "Default")
      (node (ref "IC10") (pin "128") (pinfunction "PB4/5_128") (pintype "input"))
      (node (ref "IC11") (pin "28") (pinfunction "PB10_28") (pintype "bidirectional"))
      (node (ref "RN11") (pin "1") (pinfunction "1_1") (pintype "passive"))
      (node (ref "S1") (pin "3") (pinfunction "3_3") (pintype "passive"))
    )
    (net (code "66") (name "INTSIG17") (class "Default")
      (node (ref "IC10") (pin "126") (pinfunction "PB4/2_126") (pintype "input"))
      (node (ref "IC11") (pin "29") (pinfunction "PB11_29") (pintype "bidirectional"))
      (node (ref "RN11") (pin "2") (pinfunction "2_2") (pintype "passive"))
      (node (ref "S1") (pin "4") (pinfunction "4_4") (pintype "passive"))
    )
    (net (code "67") (name "INTSIG18") (class "Default")
      (node (ref "IC10") (pin "88") (pinfunction "PB7/17_88") (pintype "input"))
      (node (ref "IC11") (pin "61") (pinfunction "PB8_61") (pintype "bidirectional"))
    )
    (net (code "68") (name "INTSIG19") (class "Default")
      (node (ref "IC10") (pin "87") (pinfunction "PB7/15_87") (pintype "input"))
      (node (ref "IC11") (pin "62") (pinfunction "PB9_62") (pintype "bidirectional"))
    )
    (net (code "69") (name "INTSIG20") (class "Default")
      (node (ref "IC10") (pin "86") (pinfunction "PB7/14_86") (pintype "input"))
      (node (ref "IC11") (pin "11") (pinfunction "PC3_11") (pintype "bidirectional"))
    )
    (net (code "70") (name "INTSIG21") (class "Default")
      (node (ref "IC10") (pin "85") (pinfunction "PB7/12_85") (pintype "input"))
      (node (ref "IC11") (pin "10") (pinfunction "PC2_10") (pintype "bidirectional"))
    )
    (net (code "71") (name "INTSIG22") (class "Default")
      (node (ref "IC10") (pin "83") (pinfunction "PB7/16_83") (pintype "input"))
      (node (ref "IC11") (pin "9") (pinfunction "PC1_9") (pintype "bidirectional"))
    )
    (net (code "72") (name "IORQ") (class "Default")
      (node (ref "CN1") (pin "11") (pinfunction "11_11") (pintype "bidirectional"))
      (node (ref "CN2") (pin "11") (pinfunction "11_11") (pintype "bidirectional"))
      (node (ref "IC1") (pin "20") (pinfunction "IORQ_20") (pintype "output"))
      (node (ref "IC10") (pin "80") (pinfunction "PB7/9_80") (pintype "input"))
    )
    (net (code "73") (name "LED") (class "Default")
      (node (ref "IC11") (pin "34") (pinfunction "PB13_34") (pintype "bidirectional"))
      (node (ref "USB") (pin "C") (pinfunction "C_C") (pintype "passive"))
    )
    (net (code "74") (name "MREQ") (class "Default")
      (node (ref "CN1") (pin "12") (pinfunction "12_12") (pintype "bidirectional"))
      (node (ref "CN2") (pin "12") (pinfunction "12_12") (pintype "bidirectional"))
      (node (ref "IC1") (pin "19") (pinfunction "MREQ_19") (pintype "output"))
      (node (ref "IC10") (pin "78") (pinfunction "PB7/8_78") (pintype "input"))
    )
    (net (code "75") (name "MSXPORTC0") (class "Default")
      (node (ref "IC10") (pin "3") (pinfunction "PB2/6_3") (pintype "input"))
      (node (ref "IC11") (pin "14") (pinfunction "PA0-WKUP_14") (pintype "bidirectional"))
    )
    (net (code "76") (name "MSXPORTC1") (class "Default")
      (node (ref "IC10") (pin "2") (pinfunction "PB2/5_2") (pintype "input"))
      (node (ref "IC11") (pin "15") (pinfunction "PA1_15") (pintype "bidirectional"))
    )
    (net (code "77") (name "MSXPORTC2") (class "Default")
      (node (ref "IC10") (pin "143") (pinfunction "PB2/2_143") (pintype "input"))
      (node (ref "IC11") (pin "16") (pinfunction "PA2_16") (pintype "bidirectional"))
    )
    (net (code "78") (name "MSXPORTC3") (class "Default")
      (node (ref "IC10") (pin "142") (pinfunction "PB2/1_142") (pintype "input"))
      (node (ref "IC11") (pin "17") (pinfunction "PA3_17") (pintype "bidirectional"))
    )
    (net (code "79") (name "N$7") (class "Default")
      (node (ref "C63") (pin "2") (pinfunction "2_2") (pintype "passive"))
      (node (ref "R18") (pin "2") (pinfunction "2_2") (pintype "passive"))
    )
    (net (code "80") (name "NMI") (class "Default")
      (node (ref "IC1") (pin "17") (pinfunction "NMI_17") (pintype "input"))
      (node (ref "IC10") (pin "74") (pinfunction "PB7/5_74") (pintype "input"))
    )
    (net (code "81") (name "NRST") (class "Default")
      (node (ref "C7") (pin "1") (pinfunction "1_1") (pintype "passive"))
      (node (ref "IC11") (pin "7") (pinfunction "~{RST}_7") (pintype "input"))
      (node (ref "JP2") (pin "4") (pinfunction "4_4") (pintype "passive"))
      (node (ref "R2") (pin "1") (pinfunction "1_1") (pintype "passive"))
    )
    (net (code "82") (name "Net-(C41-Pad2)") (class "Default")
      (node (ref "C41") (pin "2") (pinfunction "2_2") (pintype "passive"))
      (node (ref "R1") (pin "2") (pinfunction "2_2") (pintype "passive"))
    )
    (net (code "83") (name "Net-(C42-Pad2)") (class "Default")
      (node (ref "C42") (pin "2") (pinfunction "2_2") (pintype "passive"))
      (node (ref "R8") (pin "2") (pinfunction "2_2") (pintype "passive"))
    )
    (net (code "84") (name "Net-(C43-Pad2)") (class "Default")
      (node (ref "C43") (pin "2") (pinfunction "2_2") (pintype "passive"))
      (node (ref "R9") (pin "2") (pinfunction "2_2") (pintype "passive"))
    )
    (net (code "85") (name "Net-(C58-Pad2)") (class "Default")
      (node (ref "C58") (pin "2") (pinfunction "2_2") (pintype "passive"))
      (node (ref "R16") (pin "2") (pinfunction "2_2") (pintype "passive"))
    )
    (net (code "86") (name "Net-(C59-Pad2)") (class "Default")
      (node (ref "C59") (pin "2") (pinfunction "2_2") (pintype "passive"))
      (node (ref "R22") (pin "2") (pinfunction "2_2") (pintype "passive"))
    )
    (net (code "87") (name "Net-(C61-Pad1)") (class "Default")
      (node (ref "C61") (pin "1") (pinfunction "1_1") (pintype "passive"))
      (node (ref "R21") (pin "1") (pinfunction "1_1") (pintype "passive"))
    )
    (net (code "88") (name "Net-(F1-Pad2)") (class "Default")
      (node (ref "F1") (pin "2") (pinfunction "2_2") (pintype "passive"))
      (node (ref "U$5") (pin "2-1") (pinfunction "2-1_2-1") (pintype "bidirectional"))
    )
    (net (code "89") (name "Net-(F2-Pad2)") (class "Default")
      (node (ref "F2") (pin "2") (pinfunction "2_2") (pintype "passive"))
      (node (ref "U$5") (pin "1-1") (pinfunction "1-1_1-1") (pintype "bidirectional"))
    )
    (net (code "90") (name "Net-(IC9-VBB)") (class "Default")
      (node (ref "C35") (pin "2") (pinfunction "2_2") (pintype "passive"))
      (node (ref "IC9") (pin "33") (pinfunction "VBB_33") (pintype "bidirectional"))
    )
    (net (code "91") (name "Net-(IC9-XTAL1)") (class "Default")
      (node (ref "C52") (pin "1") (pinfunction "1_1") (pintype "passive"))
      (node (ref "IC9") (pin "63") (pinfunction "XTAL1_63") (pintype "bidirectional"))
      (node (ref "Q1") (pin "2") (pinfunction "2_2") (pintype "passive"))
    )
    (net (code "92") (name "Net-(IC9-XTAL2)") (class "Default")
      (node (ref "C51") (pin "1") (pinfunction "1_1") (pintype "passive"))
      (node (ref "IC9") (pin "64") (pinfunction "XTAL2_64") (pintype "bidirectional"))
      (node (ref "Q1") (pin "1") (pinfunction "1_1") (pintype "passive"))
    )
    (net (code "93") (name "Net-(IC12-VINA-)") (class "Default")
      (node (ref "IC12") (pin "2") (pinfunction "VINA-_2") (pintype "bidirectional"))
      (node (ref "R18") (pin "1") (pinfunction "1_1") (pintype "passive"))
      (node (ref "R19") (pin "2") (pinfunction "2_2") (pintype "passive"))
    )
    (net (code "94") (name "Net-(IC12-VOUTA)") (class "Default")
      (node (ref "C59") (pin "1") (pinfunction "1_1") (pintype "passive"))
      (node (ref "IC12") (pin "1") (pinfunction "VOUTA_1") (pintype "bidirectional"))
      (node (ref "R19") (pin "1") (pinfunction "1_1") (pintype "passive"))
    )
    (net (code "95") (name "Net-(IC12-VOUTB)") (class "Default")
      (node (ref "C60") (pin "2") (pinfunction "2_2") (pintype "passive"))
      (node (ref "IC12") (pin "7") (pinfunction "VOUTB_7") (pintype "bidirectional"))
      (node (ref "R10") (pin "1") (pinfunction "1_1") (pintype "passive"))
      (node (ref "R21") (pin "2") (pinfunction "2_2") (pintype "passive"))
    )
    (net (code "96") (name "Net-(JP4-Pad3)") (class "Default")
      (node (ref "JP4") (pin "3") (pinfunction "3_3") (pintype "passive"))
      (node (ref "R6") (pin "2") (pinfunction "2_2") (pintype "passive"))
    )
    (net (code "97") (name "Net-(L1-Pad2)") (class "Default")
      (node (ref "L1") (pin "2") (pinfunction "2_2") (pintype "passive"))
      (node (ref "X1") (pin "5") (pinfunction "5_5") (pintype "passive"))
    )
    (net (code "98") (name "Net-(L2-Pad2)") (class "Default")
      (node (ref "L2") (pin "2") (pinfunction "2_2") (pintype "passive"))
      (node (ref "X1") (pin "4") (pinfunction "4_4") (pintype "passive"))
    )
    (net (code "99") (name "Net-(L3-Pad2)") (class "Default")
      (node (ref "L3") (pin "2") (pinfunction "2_2") (pintype "passive"))
      (node (ref "X1") (pin "3") (pinfunction "3_3") (pintype "passive"))
    )
    (net (code "100") (name "Net-(L4-Pad2)") (class "Default")
      (node (ref "L4") (pin "2") (pinfunction "2_2") (pintype "passive"))
      (node (ref "X1") (pin "2") (pinfunction "2_2") (pintype "passive"))
    )
    (net (code "101") (name "Net-(L5-Pad2)") (class "Default")
      (node (ref "L5") (pin "2") (pinfunction "2_2") (pintype "passive"))
      (node (ref "X3") (pin "5") (pinfunction "5_5") (pintype "passive"))
    )
    (net (code "102") (name "Net-(L6-Pad1)") (class "Default")
      (node (ref "L6") (pin "1") (pinfunction "1_1") (pintype "passive"))
      (node (ref "X1") (pin "9") (pinfunction "9_9") (pintype "passive"))
    )
    (net (code "103") (name "Net-(L7-Pad1)") (class "Default")
      (node (ref "L7") (pin "1") (pinfunction "1_1") (pintype "passive"))
      (node (ref "X1") (pin "8") (pinfunction "8_8") (pintype "passive"))
    )
    (net (code "104") (name "Net-(L8-Pad1)") (class "Default")
      (node (ref "L8") (pin "1") (pinfunction "1_1") (pintype "passive"))
      (node (ref "X1") (pin "7") (pinfunction "7_7") (pintype "passive"))
    )
    (net (code "105") (name "Net-(L9-Pad2)") (class "Default")
      (node (ref "L9") (pin "2") (pinfunction "2_2") (pintype "passive"))
      (node (ref "X3") (pin "4") (pinfunction "4_4") (pintype "passive"))
    )
    (net (code "106") (name "Net-(L10-Pad2)") (class "Default")
      (node (ref "L10") (pin "2") (pinfunction "2_2") (pintype "passive"))
      (node (ref "X3") (pin "3") (pinfunction "3_3") (pintype "passive"))
    )
    (net (code "107") (name "Net-(L11-Pad2)") (class "Default")
      (node (ref "L11") (pin "2") (pinfunction "2_2") (pintype "passive"))
      (node (ref "X3") (pin "2") (pinfunction "2_2") (pintype "passive"))
    )
    (net (code "108") (name "Net-(L12-Pad1)") (class "Default")
      (node (ref "L12") (pin "1") (pinfunction "1_1") (pintype "passive"))
      (node (ref "X3") (pin "7") (pinfunction "7_7") (pintype "passive"))
    )
    (net (code "109") (name "Net-(L13-Pad1)") (class "Default")
      (node (ref "L13") (pin "1") (pinfunction "1_1") (pintype "passive"))
      (node (ref "X3") (pin "8") (pinfunction "8_8") (pintype "passive"))
    )
    (net (code "110") (name "Net-(L14-Pad1)") (class "Default")
      (node (ref "L14") (pin "1") (pinfunction "1_1") (pintype "passive"))
      (node (ref "X3") (pin "9") (pinfunction "9_9") (pintype "passive"))
    )
    (net (code "111") (name "Net-(PWR-PadA)") (class "Default")
      (node (ref "PWR") (pin "A") (pinfunction "A_A") (pintype "passive"))
      (node (ref "R3") (pin "2") (pinfunction "2_2") (pintype "passive"))
    )
    (net (code "112") (name "Net-(RN2-Pad4)") (class "Default")
      (node (ref "RN2") (pin "4") (pinfunction "4_4") (pintype "passive"))
      (node (ref "USB") (pin "A") (pinfunction "A_A") (pintype "passive"))
    )
    (net (code "113") (name "OSCIN") (class "Default")
      (node (ref "C10") (pin "1") (pinfunction "1_1") (pintype "passive"))
      (node (ref "IC11") (pin "5") (pinfunction "PH0-OSC_IN_5") (pintype "bidirectional"))
      (node (ref "X2") (pin "2") (pinfunction "2_2") (pintype "passive"))
    )
    (net (code "114") (name "OSCOUT") (class "Default")
      (node (ref "C11") (pin "1") (pinfunction "1_1") (pintype "passive"))
      (node (ref "IC11") (pin "6") (pinfunction "PH1-OSC_OUT_6") (pintype "bidirectional"))
      (node (ref "X2") (pin "1") (pinfunction "1_1") (pintype "passive"))
    )
    (net (code "115") (name "PA9BOOT") (class "Default")
      (node (ref "IC11") (pin "42") (pinfunction "PA9_42") (pintype "bidirectional"))
      (node (ref "PA9BOOT") (pin "2") (pinfunction "2_2") (pintype "passive"))
    )
    (net (code "116") (name "PPI_SND") (class "Default")
      (node (ref "C43") (pin "1") (pinfunction "1_1") (pintype "passive"))
      (node (ref "IC10") (pin "9") (pinfunction "PB2/11_9") (pintype "input"))
    )
    (net (code "117") (name "PSGA0") (class "Default")
      (node (ref "IC13") (pin "21") (pinfunction "IOA0_21") (pintype "bidirectional"))
      (node (ref "IC15") (pin "4") (pinfunction "1Y_4") (pintype "output"))
    )
    (net (code "118") (name "PSGA1") (class "Default")
      (node (ref "IC13") (pin "20") (pinfunction "IOA1_20") (pintype "bidirectional"))
      (node (ref "IC15") (pin "7") (pinfunction "2Y_7") (pintype "output"))
    )
    (net (code "119") (name "PSGA2") (class "Default")
      (node (ref "IC13") (pin "19") (pinfunction "IOA2_19") (pintype "bidirectional"))
      (node (ref "IC15") (pin "9") (pinfunction "3Y_9") (pintype "output"))
    )
    (net (code "120") (name "PSGA3") (class "Default")
      (node (ref "IC13") (pin "18") (pinfunction "IOA3_18") (pintype "bidirectional"))
      (node (ref "IC15") (pin "12") (pinfunction "4Y_12") (pintype "output"))
    )
    (net (code "121") (name "PSGA4") (class "Default")
      (node (ref "IC13") (pin "17") (pinfunction "IOA4_17") (pintype "bidirectional"))
      (node (ref "IC16") (pin "4") (pinfunction "1Y_4") (pintype "output"))
    )
    (net (code "122") (name "PSGA5") (class "Default")
      (node (ref "IC13") (pin "16") (pinfunction "IOA5_16") (pintype "bidirectional"))
      (node (ref "IC16") (pin "7") (pinfunction "2Y_7") (pintype "output"))
    )
    (net (code "123") (name "PSGA6") (class "Default")
      (node (ref "IC13") (pin "15") (pinfunction "IOA6_15") (pintype "bidirectional"))
    )
    (net (code "124") (name "PSGA7") (class "Default")
      (node (ref "IC13") (pin "14") (pinfunction "IOA7_14") (pintype "bidirectional"))
    )
    (net (code "125") (name "PSGB0") (class "Default")
      (node (ref "IC13") (pin "13") (pinfunction "IOB0_13") (pintype "bidirectional"))
      (node (ref "IC17") (pin "3") (pinfunction "I_3") (pintype "input"))
    )
    (net (code "126") (name "PSGB1") (class "Default")
      (node (ref "IC13") (pin "12") (pinfunction "IOB1_12") (pintype "bidirectional"))
      (node (ref "IC17") (pin "1") (pinfunction "I_1") (pintype "input"))
    )
    (net (code "127") (name "PSGB2") (class "Default")
      (node (ref "IC13") (pin "11") (pinfunction "IOB2_11") (pintype "bidirectional"))
      (node (ref "IC17") (pin "5") (pinfunction "I_5") (pintype "input"))
    )
    (net (code "128") (name "PSGB3") (class "Default")
      (node (ref "IC13") (pin "10") (pinfunction "IOB3_10") (pintype "bidirectional"))
      (node (ref "IC17") (pin "9") (pinfunction "I_9") (pintype "input"))
    )
    (net (code "129") (name "PSGB6") (class "Default")
      (node (ref "IC13") (pin "7") (pinfunction "IOB6_7") (pintype "bidirectional"))
      (node (ref "IC15") (pin "1") (pinfunction "~{A}/B_1") (pintype "input"))
      (node (ref "IC16") (pin "1") (pinfunction "~{A}/B_1") (pintype "input"))
    )
    (net (code "130") (name "PSGB7") (class "Default")
      (node (ref "IC13") (pin "6") (pinfunction "IOB7_6") (pintype "bidirectional"))
    )
    (net (code "131") (name "PSGCLK") (class "Default")
      (node (ref "IC10") (pin "4") (pinfunction "PB2/4_4") (pintype "input"))
      (node (ref "IC13") (pin "22") (pinfunction "CLOCK_22") (pintype "bidirectional"))
    )
    (net (code "132") (name "PSG_AUD") (class "Default")
      (node (ref "C63") (pin "1") (pinfunction "1_1") (pintype "passive"))
      (node (ref "IC13") (pin "3") (pinfunction "ACHAN_B_3") (pintype "bidirectional"))
      (node (ref "IC13") (pin "38") (pinfunction "ACHAN_C_38") (pintype "bidirectional"))
      (node (ref "IC13") (pin "4") (pinfunction "ACHAN_A_4") (pintype "bidirectional"))
      (node (ref "R4") (pin "2") (pinfunction "2_2") (pintype "passive"))
    )
    (net (code "133") (name "RAMSLOT0") (class "Default")
      (node (ref "IC10") (pin "115") (pinfunction "PB6/10_115") (pintype "input"))
      (node (ref "IC6") (pin "30") (pinfunction "A14_30") (pintype "bidirectional"))
    )
    (net (code "134") (name "RAMSLOT1") (class "Default")
      (node (ref "IC10") (pin "120") (pinfunction "PB6/12_120") (pintype "input"))
      (node (ref "IC6") (pin "38") (pinfunction "A15_38") (pintype "bidirectional"))
    )
    (net (code "135") (name "RAMSLOT2") (class "Default")
      (node (ref "IC10") (pin "121") (pinfunction "PB6/14_121") (pintype "input"))
      (node (ref "IC6") (pin "39") (pinfunction "A16_39") (pintype "bidirectional"))
    )
    (net (code "136") (name "RAMSLOT3") (class "Default")
      (node (ref "IC10") (pin "124") (pinfunction "PB6/15_124") (pintype "input"))
      (node (ref "IC6") (pin "40") (pinfunction "A17_40") (pintype "bidirectional"))
    )
    (net (code "137") (name "RAMSLOT4") (class "Default")
      (node (ref "IC10") (pin "125") (pinfunction "PB6/17_125") (pintype "input"))
      (node (ref "IC6") (pin "41") (pinfunction "A18_41") (pintype "bidirectional"))
    )
    (net (code "138") (name "RAS") (class "Default")
      (node (ref "IC2") (pin "5") (pinfunction "~{RAS}_5") (pintype "input"))
      (node (ref "IC3") (pin "5") (pinfunction "~{RAS}_5") (pintype "input"))
      (node (ref "IC4") (pin "5") (pinfunction "~{RAS}_5") (pintype "input"))
      (node (ref "IC5") (pin "5") (pinfunction "~{RAS}_5") (pintype "input"))
      (node (ref "IC9") (pin "62") (pinfunction "~{RAS}_62") (pintype "bidirectional"))
    )
    (net (code "139") (name "RD") (class "Default")
      (node (ref "CN1") (pin "14") (pinfunction "14_14") (pintype "bidirectional"))
      (node (ref "CN2") (pin "14") (pinfunction "14_14") (pintype "bidirectional"))
      (node (ref "IC1") (pin "21") (pinfunction "RD_21") (pintype "output"))
      (node (ref "IC10") (pin "81") (pinfunction "PB7/13_81") (pintype "input"))
    )
    (net (code "140") (name "RD0") (class "Default")
      (node (ref "IC2") (pin "2") (pinfunction "I/O1_2") (pintype "bidirectional"))
      (node (ref "IC4") (pin "2") (pinfunction "I/O1_2") (pintype "bidirectional"))
      (node (ref "IC9") (pin "41") (pinfunction "RD0_41") (pintype "bidirectional"))
    )
    (net (code "141") (name "RD1") (class "Default")
      (node (ref "IC2") (pin "3") (pinfunction "I/O2_3") (pintype "bidirectional"))
      (node (ref "IC4") (pin "3") (pinfunction "I/O2_3") (pintype "bidirectional"))
      (node (ref "IC9") (pin "42") (pinfunction "RD1_42") (pintype "bidirectional"))
    )
    (net (code "142") (name "RD2") (class "Default")
      (node (ref "IC2") (pin "15") (pinfunction "I/O3_15") (pintype "bidirectional"))
      (node (ref "IC4") (pin "15") (pinfunction "I/O3_15") (pintype "bidirectional"))
      (node (ref "IC9") (pin "43") (pinfunction "RD2_43") (pintype "bidirectional"))
    )
    (net (code "143") (name "RD3") (class "Default")
      (node (ref "IC2") (pin "17") (pinfunction "I/O4_17") (pintype "bidirectional"))
      (node (ref "IC4") (pin "17") (pinfunction "I/O4_17") (pintype "bidirectional"))
      (node (ref "IC9") (pin "44") (pinfunction "RD3_44") (pintype "bidirectional"))
    )
    (net (code "144") (name "RD4") (class "Default")
      (node (ref "IC3") (pin "2") (pinfunction "I/O1_2") (pintype "bidirectional"))
      (node (ref "IC5") (pin "2") (pinfunction "I/O1_2") (pintype "bidirectional"))
      (node (ref "IC9") (pin "45") (pinfunction "RD4_45") (pintype "bidirectional"))
    )
    (net (code "145") (name "RD5") (class "Default")
      (node (ref "IC3") (pin "3") (pinfunction "I/O2_3") (pintype "bidirectional"))
      (node (ref "IC5") (pin "3") (pinfunction "I/O2_3") (pintype "bidirectional"))
      (node (ref "IC9") (pin "46") (pinfunction "RD5_46") (pintype "bidirectional"))
    )
    (net (code "146") (name "RD6") (class "Default")
      (node (ref "IC3") (pin "15") (pinfunction "I/O3_15") (pintype "bidirectional"))
      (node (ref "IC5") (pin "15") (pinfunction "I/O3_15") (pintype "bidirectional"))
      (node (ref "IC9") (pin "47") (pinfunction "RD6_47") (pintype "bidirectional"))
    )
    (net (code "147") (name "RD7") (class "Default")
      (node (ref "IC3") (pin "17") (pinfunction "I/O4_17") (pintype "bidirectional"))
      (node (ref "IC5") (pin "17") (pinfunction "I/O4_17") (pintype "bidirectional"))
      (node (ref "IC9") (pin "48") (pinfunction "RD7_48") (pintype "bidirectional"))
    )
    (net (code "148") (name "ROMA14") (class "Default")
      (node (ref "IC10") (pin "31") (pinfunction "PB1/10_31") (pintype "input"))
      (node (ref "IC7") (pin "29") (pinfunction "A14_29") (pintype "bidirectional"))
    )
    (net (code "149") (name "ROMA15") (class "Default")
      (node (ref "IC10") (pin "28") (pinfunction "PB1/15_28") (pintype "input"))
      (node (ref "IC7") (pin "3") (pinfunction "A15_3") (pintype "bidirectional"))
    )
    (net (code "150") (name "ROMA16") (class "Default")
      (node (ref "IC10") (pin "27") (pinfunction "PB1/14_27") (pintype "input"))
      (node (ref "IC7") (pin "2") (pinfunction "A16_2") (pintype "bidirectional"))
    )
    (net (code "151") (name "ROMA17") (class "Default")
      (node (ref "IC10") (pin "25") (pinfunction "PB1/4_25") (pintype "input"))
      (node (ref "IC7") (pin "30") (pinfunction "A17_30") (pintype "bidirectional"))
    )
    (net (code "152") (name "ROMA18") (class "Default")
      (node (ref "IC10") (pin "32") (pinfunction "PB3/2/GCK2_32") (pintype "input"))
      (node (ref "IC7") (pin "1") (pinfunction "VPP_1") (pintype "bidirectional"))
    )
    (net (code "153") (name "ROMOE") (class "Default")
      (node (ref "IC10") (pin "26") (pinfunction "PB1/12_26") (pintype "input"))
      (node (ref "IC7") (pin "24") (pinfunction "~{OE}_24") (pintype "bidirectional"))
    )
    (net (code "154") (name "R_O") (class "Default")
      (node (ref "IC9") (pin "23") (pinfunction "R_23") (pintype "bidirectional"))
      (node (ref "U$3") (pin "P$4") (pinfunction "P$4_P$4") (pintype "bidirectional"))
      (node (ref "VIDEO") (pin "4") (pinfunction "4_4") (pintype "passive"))
    )
    (net (code "155") (name "SA0") (class "Default")
      (node (ref "IC10") (pin "92") (pinfunction "PB8/5_92") (pintype "input"))
      (node (ref "IC6") (pin "3") (pinfunction "A0_3") (pintype "bidirectional"))
    )
    (net (code "156") (name "SA1") (class "Default")
      (node (ref "IC10") (pin "93") (pinfunction "PB8/6_93") (pintype "input"))
      (node (ref "IC6") (pin "4") (pinfunction "A1_4") (pintype "bidirectional"))
    )
    (net (code "157") (name "SA2") (class "Default")
      (node (ref "IC10") (pin "94") (pinfunction "PB8/8_94") (pintype "input"))
      (node (ref "IC6") (pin "5") (pinfunction "A2_5") (pintype "bidirectional"))
    )
    (net (code "158") (name "SA3") (class "Default")
      (node (ref "IC10") (pin "95") (pinfunction "PB8/3_95") (pintype "input"))
      (node (ref "IC6") (pin "6") (pinfunction "A3_6") (pintype "bidirectional"))
    )
    (net (code "159") (name "SA4") (class "Default")
      (node (ref "IC10") (pin "96") (pinfunction "PB8/9_96") (pintype "input"))
      (node (ref "IC6") (pin "7") (pinfunction "A4_7") (pintype "bidirectional"))
    )
    (net (code "160") (name "SA5") (class "Default")
      (node (ref "IC10") (pin "103") (pinfunction "PB8/13_103") (pintype "input"))
      (node (ref "IC6") (pin "16") (pinfunction "A5_16") (pintype "bidirectional"))
    )
    (net (code "161") (name "SA6") (class "Default")
      (node (ref "IC10") (pin "104") (pinfunction "PB8/15_104") (pintype "input"))
      (node (ref "IC6") (pin "17") (pinfunction "A6_17") (pintype "bidirectional"))
    )
    (net (code "162") (name "SA7") (class "Default")
      (node (ref "IC10") (pin "105") (pinfunction "PB8/17_105") (pintype "input"))
      (node (ref "IC6") (pin "18") (pinfunction "A7_18") (pintype "bidirectional"))
    )
    (net (code "163") (name "SA8") (class "Default")
      (node (ref "IC10") (pin "106") (pinfunction "PB6/2_106") (pintype "input"))
      (node (ref "IC6") (pin "19") (pinfunction "A8_19") (pintype "bidirectional"))
    )
    (net (code "164") (name "SA9") (class "Default")
      (node (ref "IC10") (pin "107") (pinfunction "PB8/16_107") (pintype "input"))
      (node (ref "IC6") (pin "20") (pinfunction "A9_20") (pintype "bidirectional"))
    )
    (net (code "165") (name "SA10") (class "Default")
      (node (ref "IC10") (pin "110") (pinfunction "PB6/5_110") (pintype "input"))
      (node (ref "IC6") (pin "26") (pinfunction "A10_26") (pintype "bidirectional"))
    )
    (net (code "166") (name "SA11") (class "Default")
      (node (ref "IC10") (pin "111") (pinfunction "PB6/4_111") (pintype "input"))
      (node (ref "IC6") (pin "27") (pinfunction "A11_27") (pintype "bidirectional"))
    )
    (net (code "167") (name "SA12") (class "Default")
      (node (ref "IC10") (pin "112") (pinfunction "PB6/6_112") (pintype "input"))
      (node (ref "IC6") (pin "28") (pinfunction "A12_28") (pintype "bidirectional"))
    )
    (net (code "168") (name "SA13") (class "Default")
      (node (ref "IC10") (pin "113") (pinfunction "PB6/8_113") (pintype "input"))
      (node (ref "IC6") (pin "29") (pinfunction "A13_29") (pintype "bidirectional"))
    )
    (net (code "169") (name "SD0") (class "Default")
      (node (ref "IC10") (pin "98") (pinfunction "PB8/11_98") (pintype "input"))
      (node (ref "IC6") (pin "9") (pinfunction "I/O1_9") (pintype "bidirectional"))
    )
    (net (code "170") (name "SD1") (class "Default")
      (node (ref "IC10") (pin "100") (pinfunction "PB8/12_100") (pintype "input"))
      (node (ref "IC6") (pin "10") (pinfunction "I/O2_10") (pintype "bidirectional"))
    )
    (net (code "171") (name "SD2") (class "Default")
      (node (ref "IC10") (pin "101") (pinfunction "PB8/10_101") (pintype "input"))
      (node (ref "IC6") (pin "13") (pinfunction "I/O3_13") (pintype "bidirectional"))
    )
    (net (code "172") (name "SD3") (class "Default")
      (node (ref "IC10") (pin "102") (pinfunction "PB8/14_102") (pintype "input"))
      (node (ref "IC6") (pin "14") (pinfunction "I/O4_14") (pintype "bidirectional"))
    )
    (net (code "173") (name "SD4") (class "Default")
      (node (ref "IC10") (pin "116") (pinfunction "PB6/9_116") (pintype "input"))
      (node (ref "IC6") (pin "31") (pinfunction "I/O5_31") (pintype "bidirectional"))
    )
    (net (code "174") (name "SD5") (class "Default")
      (node (ref "IC10") (pin "117") (pinfunction "PB6/16_117") (pintype "input"))
      (node (ref "IC6") (pin "32") (pinfunction "I/O6_32") (pintype "bidirectional"))
    )
    (net (code "175") (name "SD6") (class "Default")
      (node (ref "IC10") (pin "118") (pinfunction "PB4/1_118") (pintype "input"))
      (node (ref "IC6") (pin "35") (pinfunction "I/O7_35") (pintype "bidirectional"))
    )
    (net (code "176") (name "SD7") (class "Default")
      (node (ref "IC10") (pin "119") (pinfunction "PB6/11_119") (pintype "input"))
      (node (ref "IC6") (pin "36") (pinfunction "I/O8_36") (pintype "bidirectional"))
    )
    (net (code "177") (name "SLOTCLK") (class "Default")
      (node (ref "CN1") (pin "42") (pinfunction "42_42") (pintype "bidirectional"))
      (node (ref "CN2") (pin "42") (pinfunction "42_42") (pintype "bidirectional"))
      (node (ref "IC10") (pin "17") (pinfunction "PB1/3_17") (pintype "input"))
    )
    (net (code "178") (name "SND_IN1") (class "Default")
      (node (ref "C41") (pin "1") (pinfunction "1_1") (pintype "passive"))
      (node (ref "CN1") (pin "49") (pinfunction "49_49") (pintype "bidirectional"))
    )
    (net (code "179") (name "SND_IN2") (class "Default")
      (node (ref "C42") (pin "1") (pinfunction "1_1") (pintype "passive"))
      (node (ref "CN2") (pin "49") (pinfunction "49_49") (pintype "bidirectional"))
    )
    (net (code "180") (name "SW1") (class "Default")
      (node (ref "IC11") (pin "39") (pinfunction "PC8_39") (pintype "bidirectional"))
      (node (ref "RN11") (pin "3") (pinfunction "3_3") (pintype "passive"))
      (node (ref "S2") (pin "4") (pinfunction "4_4") (pintype "passive"))
    )
    (net (code "181") (name "SW2") (class "Default")
      (node (ref "IC11") (pin "40") (pinfunction "PC9_40") (pintype "bidirectional"))
      (node (ref "RN11") (pin "4") (pinfunction "4_4") (pintype "passive"))
      (node (ref "S2") (pin "3") (pinfunction "3_3") (pintype "passive"))
    )
    (net (code "182") (name "SWCLK") (class "Default")
      (node (ref "IC11") (pin "49") (pinfunction "PA14(JTCK-SWCLK)_49") (pintype "bidirectional"))
      (node (ref "JP2") (pin "5") (pinfunction "5_5") (pintype "passive"))
    )
    (net (code "183") (name "SWDIO") (class "Default")
      (node (ref "IC11") (pin "46") (pinfunction "PA13(JTMS-SWDIO)_46") (pintype "bidirectional"))
      (node (ref "JP2") (pin "6") (pinfunction "6_6") (pintype "passive"))
    )
    (net (code "184") (name "SWR") (class "Default")
      (node (ref "IC10") (pin "91") (pinfunction "PB8/2_91") (pintype "input"))
      (node (ref "IC6") (pin "15") (pinfunction "~{WE}_15") (pintype "bidirectional"))
    )
    (net (code "185") (name "TCK") (class "Default")
      (node (ref "IC10") (pin "67") (pinfunction "TCK_67") (pintype "input"))
      (node (ref "JTAG1") (pin "4") (pinfunction "4_4") (pintype "passive"))
    )
    (net (code "186") (name "TDI") (class "Default")
      (node (ref "IC10") (pin "63") (pinfunction "TDI_63") (pintype "input"))
      (node (ref "JTAG1") (pin "2") (pinfunction "2_2") (pintype "passive"))
    )
    (net (code "187") (name "TDO") (class "Default")
      (node (ref "IC10") (pin "122") (pinfunction "TDO_122") (pintype "input"))
      (node (ref "JTAG1") (pin "3") (pinfunction "3_3") (pintype "passive"))
    )
    (net (code "188") (name "TMS") (class "Default")
      (node (ref "IC10") (pin "65") (pinfunction "TMS_65") (pintype "input"))
      (node (ref "JTAG1") (pin "1") (pinfunction "1_1") (pintype "passive"))
    )
    (net (code "189") (name "UART5_RX") (class "Default")
      (node (ref "IC11") (pin "54") (pinfunction "PD2_54") (pintype "bidirectional"))
      (node (ref "UART") (pin "1") (pinfunction "1_1") (pintype "passive"))
    )
    (net (code "190") (name "UART5_TX") (class "Default")
      (node (ref "IC11") (pin "53") (pinfunction "PC12_53") (pintype "bidirectional"))
      (node (ref "UART") (pin "2") (pinfunction "2_2") (pintype "passive"))
    )
    (net (code "191") (name "USB1_DM") (class "Default")
      (node (ref "IC11") (pin "44") (pinfunction "PA11_44") (pintype "bidirectional"))
      (node (ref "U$5") (pin "2-2") (pinfunction "2-2_2-2") (pintype "bidirectional"))
    )
    (net (code "192") (name "USB1_DP") (class "Default")
      (node (ref "IC11") (pin "45") (pinfunction "PA12_45") (pintype "bidirectional"))
      (node (ref "U$5") (pin "2-3") (pinfunction "2-3_2-3") (pintype "bidirectional"))
    )
    (net (code "193") (name "USB2_DM") (class "Default")
      (node (ref "IC11") (pin "35") (pinfunction "PB14_35") (pintype "bidirectional"))
      (node (ref "U$5") (pin "1-2") (pinfunction "1-2_1-2") (pintype "bidirectional"))
    )
    (net (code "194") (name "USB2_DP") (class "Default")
      (node (ref "IC11") (pin "36") (pinfunction "PB15_36") (pintype "bidirectional"))
      (node (ref "U$5") (pin "1-3") (pinfunction "1-3_1-3") (pintype "bidirectional"))
    )
    (net (code "195") (name "V%") (class "Default")
      (node (ref "R11") (pin "1") (pinfunction "1_1") (pintype "passive"))
      (node (ref "R12") (pin "2") (pinfunction "2_2") (pintype "passive"))
      (node (ref "TP3") (pin "TP") (pinfunction "TP_TP") (pintype "input"))
    )
    (net (code "196") (name "VCAP") (class "Default")
      (node (ref "C22") (pin "1") (pinfunction "1_1") (pintype "passive"))
      (node (ref "IC11") (pin "30") (pinfunction "VCAP_1_30") (pintype "power_in"))
    )
    (net (code "197") (name "VCC") (class "Default")
      (node (ref "C1") (pin "1") (pinfunction "1_1") (pintype "passive"))
      (node (ref "C15") (pin "2") (pinfunction "2_2") (pintype "passive"))
      (node (ref "C17") (pin "2") (pinfunction "2_2") (pintype "passive"))
      (node (ref "C18") (pin "2") (pinfunction "2_2") (pintype "passive"))
      (node (ref "C19") (pin "2") (pinfunction "2_2") (pintype "passive"))
      (node (ref "C20") (pin "2") (pinfunction "2_2") (pintype "passive"))
      (node (ref "C21") (pin "2") (pinfunction "2_2") (pintype "passive"))
      (node (ref "C23") (pin "2") (pinfunction "2_2") (pintype "passive"))
      (node (ref "C24") (pin "1") (pinfunction "+_1") (pintype "bidirectional"))
      (node (ref "C25") (pin "1") (pinfunction "1_1") (pintype "passive"))
      (node (ref "C26") (pin "2") (pinfunction "2_2") (pintype "passive"))
      (node (ref "C27") (pin "2") (pinfunction "2_2") (pintype "passive"))
      (node (ref "C3") (pin "1") (pinfunction "1_1") (pintype "passive"))
      (node (ref "C37") (pin "2") (pinfunction "2_2") (pintype "passive"))
      (node (ref "C38") (pin "2") (pinfunction "2_2") (pintype "passive"))
      (node (ref "C39") (pin "2") (pinfunction "2_2") (pintype "passive"))
      (node (ref "C40") (pin "2") (pinfunction "2_2") (pintype "passive"))
      (node (ref "C45") (pin "1") (pinfunction "+_1") (pintype "bidirectional"))
      (node (ref "C46") (pin "1") (pinfunction "+_1") (pintype "bidirectional"))
      (node (ref "C47") (pin "1") (pinfunction "+_1") (pintype "bidirectional"))
      (node (ref "C48") (pin "2") (pinfunction "2_2") (pintype "passive"))
      (node (ref "C49") (pin "2") (pinfunction "2_2") (pintype "passive"))
      (node (ref "C50") (pin "2") (pinfunction "2_2") (pintype "passive"))
      (node (ref "C53") (pin "2") (pinfunction "2_2") (pintype "passive"))
      (node (ref "C54") (pin "2") (pinfunction "2_2") (pintype "passive"))
      (node (ref "C55") (pin "2") (pinfunction "2_2") (pintype "passive"))
      (node (ref "C56") (pin "2") (pinfunction "2_2") (pintype "passive"))
      (node (ref "C57") (pin "2") (pinfunction "2_2") (pintype "passive"))
      (node (ref "C62") (pin "1") (pinfunction "1_1") (pintype "passive"))
      (node (ref "CN1") (pin "45") (pinfunction "45_45") (pintype "bidirectional"))
      (node (ref "CN1") (pin "47") (pinfunction "47_47") (pintype "bidirectional"))
      (node (ref "CN2") (pin "45") (pinfunction "45_45") (pintype "bidirectional"))
      (node (ref "CN2") (pin "47") (pinfunction "47_47") (pintype "bidirectional"))
      (node (ref "F1") (pin "1") (pinfunction "1_1") (pintype "passive"))
      (node (ref "F2") (pin "1") (pinfunction "1_1") (pintype "passive"))
      (node (ref "IC1") (pin "11") (pinfunction "VCC_11") (pintype "power_in"))
      (node (ref "IC12") (pin "8") (pinfunction "VDD_8") (pintype "bidirectional"))
      (node (ref "IC13") (pin "25") (pinfunction "A8_25") (pintype "bidirectional"))
      (node (ref "IC13") (pin "40") (pinfunction "VCC_40") (pintype "bidirectional"))
      (node (ref "IC14") (pin "5") (pinfunction "VCC_5") (pintype "power_in"))
      (node (ref "IC2") (pin "9") (pinfunction "VCC_9") (pintype "power_in"))
      (node (ref "IC3") (pin "9") (pinfunction "VCC_9") (pintype "power_in"))
      (node (ref "IC4") (pin "9") (pinfunction "VCC_9") (pintype "power_in"))
      (node (ref "IC5") (pin "9") (pinfunction "VCC_9") (pintype "power_in"))
      (node (ref "IC7") (pin "31") (pinfunction "~{PGM}_31") (pintype "bidirectional"))
      (node (ref "IC7") (pin "32") (pinfunction "VCC_32") (pintype "bidirectional"))
      (node (ref "IC8") (pin "3") (pinfunction "IN_3") (pintype "input"))
      (node (ref "IC9") (pin "27") (pinfunction "~{HRESET}_27") (pintype "bidirectional"))
      (node (ref "IC9") (pin "58") (pinfunction "VDD_58") (pintype "bidirectional"))
      (node (ref "J1") (pin "1") (pinfunction "1_1") (pintype "passive"))
      (node (ref "JP2") (pin "1") (pinfunction "1_1") (pintype "passive"))
      (node (ref "JP4") (pin "2") (pinfunction "2_2") (pintype "passive"))
      (node (ref "JP5") (pin "1") (pinfunction "1_1") (pintype "passive"))
      (node (ref "JP6") (pin "1") (pinfunction "1_1") (pintype "passive"))
      (node (ref "PA9BOOT") (pin "3") (pinfunction "3_3") (pintype "passive"))
      (node (ref "POWR") (pin "1") (pinfunction "1_1") (pintype "passive"))
      (node (ref "R11") (pin "2") (pinfunction "2_2") (pintype "passive"))
      (node (ref "R13") (pin "1") (pinfunction "1_1") (pintype "passive"))
      (node (ref "R15") (pin "2") (pinfunction "2_2") (pintype "passive"))
      (node (ref "R17") (pin "2") (pinfunction "2_2") (pintype "passive"))
      (node (ref "RN1") (pin "5") (pinfunction "5_5") (pintype "passive"))
      (node (ref "RN1") (pin "6") (pinfunction "6_6") (pintype "passive"))
      (node (ref "RN1") (pin "7") (pinfunction "7_7") (pintype "passive"))
      (node (ref "RN1") (pin "8") (pinfunction "8_8") (pintype "passive"))
      (node (ref "RN10") (pin "5") (pinfunction "5_5") (pintype "passive"))
      (node (ref "RN10") (pin "6") (pinfunction "6_6") (pintype "passive"))
      (node (ref "RN10") (pin "7") (pinfunction "7_7") (pintype "passive"))
      (node (ref "RN10") (pin "8") (pinfunction "8_8") (pintype "passive"))
      (node (ref "RN11") (pin "5") (pinfunction "5_5") (pintype "passive"))
      (node (ref "RN11") (pin "6") (pinfunction "6_6") (pintype "passive"))
      (node (ref "RN11") (pin "7") (pinfunction "7_7") (pintype "passive"))
      (node (ref "RN11") (pin "8") (pinfunction "8_8") (pintype "passive"))
      (node (ref "RN2") (pin "5") (pinfunction "5_5") (pintype "passive"))
      (node (ref "RN2") (pin "6") (pinfunction "6_6") (pintype "passive"))
      (node (ref "RN2") (pin "7") (pinfunction "7_7") (pintype "passive"))
      (node (ref "RN2") (pin "8") (pinfunction "8_8") (pintype "passive"))
      (node (ref "RN3") (pin "5") (pinfunction "5_5") (pintype "passive"))
      (node (ref "RN3") (pin "6") (pinfunction "6_6") (pintype "passive"))
      (node (ref "RN3") (pin "7") (pinfunction "7_7") (pintype "passive"))
      (node (ref "RN3") (pin "8") (pinfunction "8_8") (pintype "passive"))
      (node (ref "RN4") (pin "5") (pinfunction "5_5") (pintype "passive"))
      (node (ref "RN4") (pin "6") (pinfunction "6_6") (pintype "passive"))
      (node (ref "RN4") (pin "7") (pinfunction "7_7") (pintype "passive"))
      (node (ref "RN4") (pin "8") (pinfunction "8_8") (pintype "passive"))
      (node (ref "RN5") (pin "5") (pinfunction "5_5") (pintype "passive"))
      (node (ref "RN5") (pin "6") (pinfunction "6_6") (pintype "passive"))
      (node (ref "RN5") (pin "7") (pinfunction "7_7") (pintype "passive"))
      (node (ref "RN5") (pin "8") (pinfunction "8_8") (pintype "passive"))
      (node (ref "RN6") (pin "5") (pinfunction "5_5") (pintype "passive"))
      (node (ref "RN6") (pin "6") (pinfunction "6_6") (pintype "passive"))
      (node (ref "RN6") (pin "7") (pinfunction "7_7") (pintype "passive"))
      (node (ref "RN6") (pin "8") (pinfunction "8_8") (pintype "passive"))
      (node (ref "RN7") (pin "5") (pinfunction "5_5") (pintype "passive"))
      (node (ref "RN7") (pin "6") (pinfunction "6_6") (pintype "passive"))
      (node (ref "RN7") (pin "7") (pinfunction "7_7") (pintype "passive"))
      (node (ref "RN7") (pin "8") (pinfunction "8_8") (pintype "passive"))
      (node (ref "RN8") (pin "5") (pinfunction "5_5") (pintype "passive"))
      (node (ref "RN8") (pin "6") (pinfunction "6_6") (pintype "passive"))
      (node (ref "RN8") (pin "7") (pinfunction "7_7") (pintype "passive"))
      (node (ref "RN8") (pin "8") (pinfunction "8_8") (pintype "passive"))
      (node (ref "RN9") (pin "5") (pinfunction "5_5") (pintype "passive"))
      (node (ref "RN9") (pin "6") (pinfunction "6_6") (pintype "passive"))
      (node (ref "RN9") (pin "7") (pinfunction "7_7") (pintype "passive"))
      (node (ref "RN9") (pin "8") (pinfunction "8_8") (pintype "passive"))
      (node (ref "U$3") (pin "P$1") (pinfunction "P$1_P$1") (pintype "bidirectional"))
      (node (ref "X1") (pin "1") (pinfunction "1_1") (pintype "passive"))
      (node (ref "X3") (pin "1") (pinfunction "1_1") (pintype "passive"))
    )
    (net (code "198") (name "VCC-12V") (class "Default")
      (node (ref "CN1") (pin "50") (pinfunction "50_50") (pintype "bidirectional"))
      (node (ref "CN2") (pin "50") (pinfunction "50_50") (pintype "bidirectional"))
    )
    (net (code "199") (name "VCC2.5V") (class "Default")
      (node (ref "C44") (pin "2") (pinfunction "2_2") (pintype "passive"))
      (node (ref "IC12") (pin "3") (pinfunction "VINA+_3") (pintype "bidirectional"))
      (node (ref "IC12") (pin "5") (pinfunction "VINB+_5") (pintype "bidirectional"))
      (node (ref "R13") (pin "2") (pinfunction "2_2") (pintype "passive"))
      (node (ref "R14") (pin "1") (pinfunction "1_1") (pintype "passive"))
    )
    (net (code "200") (name "VCC3.3V") (class "Default")
      (node (ref "BOOT0") (pin "3") (pinfunction "3_3") (pintype "passive"))
      (node (ref "C12") (pin "1") (pinfunction "1_1") (pintype "passive"))
      (node (ref "C13") (pin "1") (pinfunction "1_1") (pintype "passive"))
      (node (ref "C14") (pin "1") (pinfunction "1_1") (pintype "passive"))
      (node (ref "C16") (pin "1") (pinfunction "1_1") (pintype "passive"))
      (node (ref "C2") (pin "1") (pinfunction "1_1") (pintype "passive"))
      (node (ref "C28") (pin "1") (pinfunction "1_1") (pintype "passive"))
      (node (ref "C29") (pin "1") (pinfunction "1_1") (pintype "passive"))
      (node (ref "C30") (pin "1") (pinfunction "1_1") (pintype "passive"))
      (node (ref "C31") (pin "1") (pinfunction "1_1") (pintype "passive"))
      (node (ref "C32") (pin "1") (pinfunction "1_1") (pintype "passive"))
      (node (ref "C33") (pin "1") (pinfunction "1_1") (pintype "passive"))
      (node (ref "C34") (pin "1") (pinfunction "1_1") (pintype "passive"))
      (node (ref "C36") (pin "1") (pinfunction "1_1") (pintype "passive"))
      (node (ref "C4") (pin "1") (pinfunction "1_1") (pintype "passive"))
      (node (ref "C5") (pin "1") (pinfunction "1_1") (pintype "passive"))
      (node (ref "C6") (pin "1") (pinfunction "1_1") (pintype "passive"))
      (node (ref "C8") (pin "1") (pinfunction "1_1") (pintype "passive"))
      (node (ref "C9") (pin "1") (pinfunction "1_1") (pintype "passive"))
      (node (ref "IC10") (pin "1") (pinfunction "VCCIO(1)_1") (pintype "input"))
      (node (ref "IC10") (pin "109") (pinfunction "VCCIO(5)_109") (pintype "input"))
      (node (ref "IC10") (pin "127") (pinfunction "VCCIO(6)_127") (pintype "input"))
      (node (ref "IC10") (pin "141") (pinfunction "VCCINT(4)_141") (pintype "input"))
      (node (ref "IC10") (pin "37") (pinfunction "VCCIO(2)_37") (pintype "input"))
      (node (ref "IC10") (pin "42") (pinfunction "VCCINT(2)_42") (pintype "input"))
      (node (ref "IC10") (pin "55") (pinfunction "VCCIO(3)_55") (pintype "input"))
      (node (ref "IC10") (pin "73") (pinfunction "VCCIO(4)_73") (pintype "input"))
      (node (ref "IC10") (pin "8") (pinfunction "VCCINT(1)_8") (pintype "input"))
      (node (ref "IC10") (pin "84") (pinfunction "VCCINT(3)_84") (pintype "input"))
      (node (ref "IC11") (pin "1") (pinfunction "VBAT_1") (pintype "power_in"))
      (node (ref "IC11") (pin "13") (pinfunction "VREF+_13") (pintype "power_in"))
      (node (ref "IC11") (pin "19") (pinfunction "VDD_19") (pintype "power_in"))
      (node (ref "IC11") (pin "32") (pinfunction "VDD_32") (pintype "power_in"))
      (node (ref "IC11") (pin "48") (pinfunction "VDD_48") (pintype "power_in"))
      (node (ref "IC11") (pin "64") (pinfunction "VDD_64") (pintype "power_in"))
      (node (ref "IC6") (pin "11") (pinfunction "VCC_1_11") (pintype "bidirectional"))
      (node (ref "IC6") (pin "33") (pinfunction "VCC_2_33") (pintype "bidirectional"))
      (node (ref "IC8") (pin "2") (pinfunction "OUT_2") (pintype "passive"))
      (node (ref "IC8") (pin "TAB") (pinfunction "OUT1_TAB") (pintype "passive"))
      (node (ref "JP2") (pin "3") (pinfunction "3_3") (pintype "passive"))
      (node (ref "JTAG1") (pin "6") (pinfunction "6_6") (pintype "passive"))
      (node (ref "OSC2") (pin "4") (pinfunction "VCC_4") (pintype "power_in"))
      (node (ref "R2") (pin "2") (pinfunction "2_2") (pintype "passive"))
      (node (ref "R3") (pin "1") (pinfunction "1_1") (pintype "passive"))
    )
    (net (code "201") (name "VCC12V") (class "Default")
      (node (ref "CN1") (pin "48") (pinfunction "48_48") (pintype "bidirectional"))
      (node (ref "CN2") (pin "48") (pinfunction "48_48") (pintype "bidirectional"))
    )
    (net (code "202") (name "VDPSEL") (class "Default")
      (node (ref "IC10") (pin "6") (pinfunction "PB2/9_6") (pintype "input"))
      (node (ref "R6") (pin "1") (pinfunction "1_1") (pintype "passive"))
      (node (ref "R7") (pin "2") (pinfunction "2_2") (pintype "passive"))
    )
    (net (code "203") (name "VID_CSYNC") (class "Default")
      (node (ref "IC9") (pin "6") (pinfunction "~{CSYNC}_6") (pintype "bidirectional"))
      (node (ref "JP3") (pin "1") (pinfunction "1_1") (pintype "passive"))
      (node (ref "R5") (pin "2") (pinfunction "2_2") (pintype "passive"))
    )
    (net (code "204") (name "VID_HSYNC") (class "Default")
      (node (ref "IC9") (pin "5") (pinfunction "~{HSYNC}_5") (pintype "bidirectional"))
      (node (ref "VIDEO") (pin "2") (pinfunction "2_2") (pintype "passive"))
    )
    (net (code "205") (name "VID_SYNC") (class "Default")
      (node (ref "JP3") (pin "2") (pinfunction "2_2") (pintype "passive"))
      (node (ref "R5") (pin "1") (pinfunction "1_1") (pintype "passive"))
      (node (ref "U$3") (pin "P$3") (pinfunction "P$3_P$3") (pintype "bidirectional"))
      (node (ref "VIDEO") (pin "3") (pinfunction "3_3") (pintype "passive"))
    )
    (net (code "206") (name "WAIT") (class "Default")
      (node (ref "CN1") (pin "7") (pinfunction "7_7") (pintype "bidirectional"))
      (node (ref "CN2") (pin "7") (pinfunction "7_7") (pintype "bidirectional"))
      (node (ref "IC1") (pin "24") (pinfunction "WAIT_24") (pintype "input"))
      (node (ref "IC10") (pin "75") (pinfunction "PB7/3_75") (pintype "input"))
      (node (ref "R17") (pin "1") (pinfunction "1_1") (pintype "passive"))
    )
    (net (code "207") (name "WR") (class "Default")
      (node (ref "CN1") (pin "13") (pinfunction "13_13") (pintype "bidirectional"))
      (node (ref "CN2") (pin "13") (pinfunction "13_13") (pintype "bidirectional"))
      (node (ref "IC1") (pin "22") (pinfunction "WR_22") (pintype "output"))
      (node (ref "IC10") (pin "79") (pinfunction "PB7/10_79") (pintype "input"))
    )
    (net (code "208") (name "YMBC1") (class "Default")
      (node (ref "IC10") (pin "13") (pinfunction "PB2/15_13") (pintype "input"))
      (node (ref "IC13") (pin "29") (pinfunction "BC1_29") (pintype "bidirectional"))
    )
    (net (code "209") (name "YMBC2") (class "Default")
      (node (ref "IC10") (pin "12") (pinfunction "PB2/13_12") (pintype "input"))
      (node (ref "IC13") (pin "28") (pinfunction "BC2_28") (pintype "bidirectional"))
    )
    (net (code "210") (name "YMBDIR") (class "Default")
      (node (ref "IC10") (pin "11") (pinfunction "PB2/14_11") (pintype "input"))
      (node (ref "IC13") (pin "27") (pinfunction "BDIR_27") (pintype "bidirectional"))
    )
    (net (code "211") (name "YMSEL") (class "Default")
      (node (ref "IC10") (pin "10") (pinfunction "PB2/12_10") (pintype "input"))
      (node (ref "IC13") (pin "26") (pinfunction "/CS_26") (pintype "bidirectional"))
    )
    (net (code "212") (name "unconnected-(CN1-Pad5)") (class "Default")
      (node (ref "CN1") (pin "5") (pinfunction "5_5") (pintype "bidirectional"))
    )
    (net (code "213") (name "unconnected-(CN1-Pad16)") (class "Default")
      (node (ref "CN1") (pin "16") (pinfunction "16_16") (pintype "bidirectional"))
    )
    (net (code "214") (name "unconnected-(CN2-Pad5)") (class "Default")
      (node (ref "CN2") (pin "5") (pinfunction "5_5") (pintype "bidirectional"))
    )
    (net (code "215") (name "unconnected-(CN2-Pad16)") (class "Default")
      (node (ref "CN2") (pin "16") (pinfunction "16_16") (pintype "bidirectional"))
    )
    (net (code "216") (name "unconnected-(IC6-NC_1-Pad1)") (class "Default")
      (node (ref "IC6") (pin "1") (pinfunction "NC_1_1") (pintype "bidirectional"))
    )
    (net (code "217") (name "unconnected-(IC6-NC_2-Pad2)") (class "Default")
      (node (ref "IC6") (pin "2") (pinfunction "NC_2_2") (pintype "bidirectional"))
    )
    (net (code "218") (name "unconnected-(IC6-NC_3-Pad21)") (class "Default")
      (node (ref "IC6") (pin "21") (pinfunction "NC_3_21") (pintype "bidirectional"))
    )
    (net (code "219") (name "unconnected-(IC6-NC_4-Pad22)") (class "Default")
      (node (ref "IC6") (pin "22") (pinfunction "NC_4_22") (pintype "bidirectional"))
    )
    (net (code "220") (name "unconnected-(IC6-NC_5-Pad23)") (class "Default")
      (node (ref "IC6") (pin "23") (pinfunction "NC_5_23") (pintype "bidirectional"))
    )
    (net (code "221") (name "unconnected-(IC6-NC_6-Pad24)") (class "Default")
      (node (ref "IC6") (pin "24") (pinfunction "NC_6_24") (pintype "bidirectional"))
    )
    (net (code "222") (name "unconnected-(IC6-NC_7-Pad25)") (class "Default")
      (node (ref "IC6") (pin "25") (pinfunction "NC_7_25") (pintype "bidirectional"))
    )
    (net (code "223") (name "unconnected-(IC6-NC_8-Pad42)") (class "Default")
      (node (ref "IC6") (pin "42") (pinfunction "NC_8_42") (pintype "bidirectional"))
    )
    (net (code "224") (name "unconnected-(IC6-NC_9-Pad43)") (class "Default")
      (node (ref "IC6") (pin "43") (pinfunction "NC_9_43") (pintype "bidirectional"))
    )
    (net (code "225") (name "unconnected-(IC6-NC_10-Pad44)") (class "Default")
      (node (ref "IC6") (pin "44") (pinfunction "NC_10_44") (pintype "bidirectional"))
    )
    (net (code "226") (name "unconnected-(IC9-BLEO-Pad7)") (class "Default")
      (node (ref "IC9") (pin "7") (pinfunction "BLEO_7") (pintype "bidirectional"))
    )
    (net (code "227") (name "unconnected-(IC9-C0-Pad19)") (class "Default")
      (node (ref "IC9") (pin "19") (pinfunction "C0_19") (pintype "bidirectional"))
    )
    (net (code "228") (name "unconnected-(IC9-C1-Pad18)") (class "Default")
      (node (ref "IC9") (pin "18") (pinfunction "C1_18") (pintype "bidirectional"))
    )
    (net (code "229") (name "unconnected-(IC9-C2-Pad17)") (class "Default")
      (node (ref "IC9") (pin "17") (pinfunction "C2_17") (pintype "bidirectional"))
    )
    (net (code "230") (name "unconnected-(IC9-C3-Pad16)") (class "Default")
      (node (ref "IC9") (pin "16") (pinfunction "C3_16") (pintype "bidirectional"))
    )
    (net (code "231") (name "unconnected-(IC9-C4-Pad15)") (class "Default")
      (node (ref "IC9") (pin "15") (pinfunction "C4_15") (pintype "bidirectional"))
    )
    (net (code "232") (name "unconnected-(IC9-C5-Pad14)") (class "Default")
      (node (ref "IC9") (pin "14") (pinfunction "C5_14") (pintype "bidirectional"))
    )
    (net (code "233") (name "unconnected-(IC9-C6-Pad13)") (class "Default")
      (node (ref "IC9") (pin "13") (pinfunction "C6_13") (pintype "bidirectional"))
    )
    (net (code "234") (name "unconnected-(IC9-C7-Pad12)") (class "Default")
      (node (ref "IC9") (pin "12") (pinfunction "C7_12") (pintype "bidirectional"))
    )
    (net (code "235") (name "unconnected-(IC9-CBDR-Pad11)") (class "Default")
      (node (ref "IC9") (pin "11") (pinfunction "CBDR_11") (pintype "bidirectional"))
    )
    (net (code "236") (name "unconnected-(IC9-CPUCLK-Pad8)") (class "Default")
      (node (ref "IC9") (pin "8") (pinfunction "CPUCLK_8") (pintype "bidirectional"))
    )
    (net (code "237") (name "unconnected-(IC9-YS-Pad10)") (class "Default")
      (node (ref "IC9") (pin "10") (pinfunction "YS_10") (pintype "bidirectional"))
    )
    (net (code "238") (name "unconnected-(IC9-~{CASX}-Pad59)") (class "Default")
      (node (ref "IC9") (pin "59") (pinfunction "~{CASX}_59") (pintype "bidirectional"))
    )
    (net (code "239") (name "unconnected-(IC9-~{DHCLK}-Pad2)") (class "Default")
      (node (ref "IC9") (pin "2") (pinfunction "~{DHCLK}_2") (pintype "bidirectional"))
    )
    (net (code "240") (name "unconnected-(IC9-~{DLCLK}-Pad3)") (class "Default")
      (node (ref "IC9") (pin "3") (pinfunction "~{DLCLK}_3") (pintype "bidirectional"))
    )
    (net (code "241") (name "unconnected-(IC9-~{WAIT}-Pad26)") (class "Default")
      (node (ref "IC9") (pin "26") (pinfunction "~{WAIT}_26") (pintype "bidirectional"))
    )
    (net (code "242") (name "unconnected-(IC11-PA8-Pad41)") (class "Default")
      (node (ref "IC11") (pin "41") (pinfunction "PA8_41") (pintype "bidirectional"))
    )
    (net (code "243") (name "unconnected-(IC11-PB12-Pad33)") (class "Default")
      (node (ref "IC11") (pin "33") (pinfunction "PB12_33") (pintype "bidirectional"))
    )
    (net (code "244") (name "unconnected-(IC13-TEST1-Pad39)") (class "Default")
      (node (ref "IC13") (pin "39") (pinfunction "TEST1_39") (pintype "bidirectional"))
    )
    (net (code "245") (name "unconnected-(IC16A-3Y-Pad9)") (class "Default")
      (node (ref "IC16") (pin "9") (pinfunction "3Y_9") (pintype "output"))
    )
    (net (code "246") (name "unconnected-(IC16A-4Y-Pad12)") (class "Default")
      (node (ref "IC16") (pin "12") (pinfunction "4Y_12") (pintype "output"))
    )
    (net (code "247") (name "unconnected-(OSC2-INH-Pad1)") (class "Default")
      (node (ref "OSC2") (pin "1") (pinfunction "INH_1") (pintype "bidirectional"))
    )
    (net (code "248") (name "unconnected-(RN1-Pad4)") (class "Default")
      (node (ref "RN1") (pin "4") (pinfunction "4_4") (pintype "passive"))
    )
    (net (code "249") (name "~{BACK1}") (class "Default")
      (node (ref "IC11") (pin "52") (pinfunction "PC11_52") (pintype "bidirectional"))
      (node (ref "IC15") (pin "5") (pinfunction "2A_5") (pintype "input"))
      (node (ref "JP5") (pin "6") (pinfunction "6_6") (pintype "passive"))
      (node (ref "L2") (pin "1") (pinfunction "1_1") (pintype "passive"))
      (node (ref "RN3") (pin "1") (pinfunction "1_1") (pintype "passive"))
    )
    (net (code "250") (name "~{BACK2}") (class "Default")
      (node (ref "IC15") (pin "6") (pinfunction "2B_6") (pintype "input"))
      (node (ref "JP6") (pin "6") (pinfunction "6_6") (pintype "passive"))
      (node (ref "L9") (pin "1") (pinfunction "1_1") (pintype "passive"))
      (node (ref "RN1") (pin "1") (pinfunction "1_1") (pintype "passive"))
    )
    (net (code "251") (name "~{EXCS1}") (class "Default")
      (node (ref "CN1") (pin "1") (pinfunction "1_1") (pintype "bidirectional"))
      (node (ref "CN2") (pin "1") (pinfunction "1_1") (pintype "bidirectional"))
      (node (ref "IC10") (pin "21") (pinfunction "PB1/8_21") (pintype "input"))
    )
    (net (code "252") (name "~{EXCS2}") (class "Default")
      (node (ref "CN1") (pin "2") (pinfunction "2_2") (pintype "bidirectional"))
      (node (ref "CN2") (pin "2") (pinfunction "2_2") (pintype "bidirectional"))
      (node (ref "IC10") (pin "20") (pinfunction "PB1/6_20") (pintype "input"))
    )
    (net (code "253") (name "~{EXCS12}") (class "Default")
      (node (ref "CN1") (pin "3") (pinfunction "3_3") (pintype "bidirectional"))
      (node (ref "CN2") (pin "3") (pinfunction "3_3") (pintype "bidirectional"))
      (node (ref "IC10") (pin "22") (pinfunction "PB1/9_22") (pintype "input"))
    )
    (net (code "254") (name "~{EXSLTSL1}") (class "Default")
      (node (ref "CN1") (pin "4") (pinfunction "4_4") (pintype "bidirectional"))
      (node (ref "IC10") (pin "23") (pinfunction "PB1/1_23") (pintype "input"))
    )
    (net (code "255") (name "~{EXSLTSL2}") (class "Default")
      (node (ref "CN2") (pin "4") (pinfunction "4_4") (pintype "bidirectional"))
      (node (ref "IC10") (pin "24") (pinfunction "PB1/11_24") (pintype "input"))
    )
    (net (code "256") (name "~{FWD1}") (class "Default")
      (node (ref "IC11") (pin "2") (pinfunction "PC13_2") (pintype "bidirectional"))
      (node (ref "IC15") (pin "2") (pinfunction "1A_2") (pintype "input"))
      (node (ref "JP5") (pin "8") (pinfunction "8_8") (pintype "passive"))
      (node (ref "L1") (pin "1") (pinfunction "1_1") (pintype "passive"))
      (node (ref "RN3") (pin "2") (pinfunction "2_2") (pintype "passive"))
    )
    (net (code "257") (name "~{FWD2}") (class "Default")
      (node (ref "IC15") (pin "3") (pinfunction "1B_3") (pintype "input"))
      (node (ref "JP6") (pin "8") (pinfunction "8_8") (pintype "passive"))
      (node (ref "L5") (pin "1") (pinfunction "1_1") (pintype "passive"))
      (node (ref "RN1") (pin "3") (pinfunction "3_3") (pintype "passive"))
    )
    (net (code "258") (name "~{INT}") (class "Default")
      (node (ref "IC1") (pin "16") (pinfunction "INT_16") (pintype "input"))
      (node (ref "IC10") (pin "70") (pinfunction "PB5/13_70") (pintype "input"))
    )
    (net (code "259") (name "~{LEFT1}") (class "Default")
      (node (ref "IC11") (pin "51") (pinfunction "PC10_51") (pintype "bidirectional"))
      (node (ref "IC15") (pin "11") (pinfunction "3A_11") (pintype "input"))
      (node (ref "JP5") (pin "4") (pinfunction "4_4") (pintype "passive"))
      (node (ref "L3") (pin "1") (pinfunction "1_1") (pintype "passive"))
      (node (ref "RN2") (pin "1") (pinfunction "1_1") (pintype "passive"))
    )
    (net (code "260") (name "~{LEFT2}") (class "Default")
      (node (ref "IC15") (pin "10") (pinfunction "3B_10") (pintype "input"))
      (node (ref "JP6") (pin "4") (pinfunction "4_4") (pintype "passive"))
      (node (ref "L10") (pin "1") (pinfunction "1_1") (pintype "passive"))
      (node (ref "RN5") (pin "3") (pinfunction "3_3") (pintype "passive"))
    )
    (net (code "261") (name "~{M1}") (class "Default")
      (node (ref "CN1") (pin "9") (pinfunction "9_9") (pintype "bidirectional"))
      (node (ref "CN2") (pin "9") (pinfunction "9_9") (pintype "bidirectional"))
      (node (ref "IC1") (pin "27") (pinfunction "M1_27") (pintype "output"))
      (node (ref "IC10") (pin "66") (pinfunction "PB5/7_66") (pintype "input"))
    )
    (net (code "262") (name "~{OUT1}") (class "Default")
      (node (ref "IC11") (pin "37") (pinfunction "PC6_37") (pintype "bidirectional"))
      (node (ref "IC13") (pin "9") (pinfunction "IOB4_9") (pintype "bidirectional"))
      (node (ref "JP5") (pin "3") (pinfunction "3_3") (pintype "passive"))
      (node (ref "L8") (pin "2") (pinfunction "2_2") (pintype "passive"))
      (node (ref "RN2") (pin "2") (pinfunction "2_2") (pintype "passive"))
    )
    (net (code "263") (name "~{OUT2}") (class "Default")
      (node (ref "IC13") (pin "8") (pinfunction "IOB5_8") (pintype "bidirectional"))
      (node (ref "JP6") (pin "3") (pinfunction "3_3") (pintype "passive"))
      (node (ref "L12") (pin "2") (pinfunction "2_2") (pintype "passive"))
      (node (ref "RN5") (pin "2") (pinfunction "2_2") (pintype "passive"))
    )
    (net (code "264") (name "~{P1_TRG1}") (class "Default")
      (node (ref "IC11") (pin "4") (pinfunction "PC15-OSC32_OUT_4") (pintype "bidirectional"))
      (node (ref "IC16") (pin "2") (pinfunction "1A_2") (pintype "input"))
      (node (ref "IC17") (pin "4") (pinfunction "O_4") (pintype "open_collector"))
      (node (ref "JP5") (pin "7") (pinfunction "7_7") (pintype "passive"))
      (node (ref "L6") (pin "2") (pinfunction "2_2") (pintype "passive"))
      (node (ref "RN3") (pin "3") (pinfunction "3_3") (pintype "passive"))
    )
    (net (code "265") (name "~{P1_TRG2}") (class "Default")
      (node (ref "IC11") (pin "3") (pinfunction "PC14-OSC32_IN_3") (pintype "bidirectional"))
      (node (ref "IC16") (pin "5") (pinfunction "2A_5") (pintype "input"))
      (node (ref "IC17") (pin "2") (pinfunction "O_2") (pintype "open_collector"))
      (node (ref "JP5") (pin "5") (pinfunction "5_5") (pintype "passive"))
      (node (ref "L7") (pin "2") (pinfunction "2_2") (pintype "passive"))
      (node (ref "RN3") (pin "4") (pinfunction "4_4") (pintype "passive"))
    )
    (net (code "266") (name "~{P2_TRG1}") (class "Default")
      (node (ref "IC16") (pin "3") (pinfunction "1B_3") (pintype "input"))
      (node (ref "IC17") (pin "6") (pinfunction "O_6") (pintype "open_collector"))
      (node (ref "JP6") (pin "7") (pinfunction "7_7") (pintype "passive"))
      (node (ref "L14") (pin "2") (pinfunction "2_2") (pintype "passive"))
      (node (ref "RN1") (pin "2") (pinfunction "2_2") (pintype "passive"))
    )
    (net (code "267") (name "~{P2_TRG2}") (class "Default")
      (node (ref "IC16") (pin "6") (pinfunction "2B_6") (pintype "input"))
      (node (ref "IC17") (pin "8") (pinfunction "O_8") (pintype "open_collector"))
      (node (ref "JP6") (pin "5") (pinfunction "5_5") (pintype "passive"))
      (node (ref "L13") (pin "2") (pinfunction "2_2") (pintype "passive"))
      (node (ref "RN5") (pin "4") (pinfunction "4_4") (pintype "passive"))
    )
    (net (code "268") (name "~{RESET}") (class "Default")
      (node (ref "CN1") (pin "15") (pinfunction "15_15") (pintype "bidirectional"))
      (node (ref "CN2") (pin "15") (pinfunction "15_15") (pintype "bidirectional"))
      (node (ref "IC1") (pin "26") (pinfunction "RESET_26") (pintype "input"))
      (node (ref "IC10") (pin "69") (pinfunction "PB5/17_69") (pintype "input"))
      (node (ref "IC13") (pin "23") (pinfunction "/RESET_23") (pintype "bidirectional"))
      (node (ref "IC9") (pin "9") (pinfunction "~{RESET}_9") (pintype "bidirectional"))
    )
    (net (code "269") (name "~{RFSH}") (class "Default")
      (node (ref "CN1") (pin "6") (pinfunction "6_6") (pintype "bidirectional"))
      (node (ref "CN2") (pin "6") (pinfunction "6_6") (pintype "bidirectional"))
      (node (ref "IC1") (pin "28") (pinfunction "RFSH_28") (pintype "output"))
      (node (ref "IC10") (pin "61") (pinfunction "PB5/14_61") (pintype "input"))
    )
    (net (code "270") (name "~{RIGHT1}") (class "Default")
      (node (ref "IC11") (pin "38") (pinfunction "PC7_38") (pintype "bidirectional"))
      (node (ref "IC15") (pin "14") (pinfunction "4A_14") (pintype "input"))
      (node (ref "JP5") (pin "2") (pinfunction "2_2") (pintype "passive"))
      (node (ref "L4") (pin "1") (pinfunction "1_1") (pintype "passive"))
      (node (ref "RN2") (pin "3") (pinfunction "3_3") (pintype "passive"))
    )
    (net (code "271") (name "~{RIGHT2}") (class "Default")
      (node (ref "IC15") (pin "13") (pinfunction "4B_13") (pintype "input"))
      (node (ref "JP6") (pin "2") (pinfunction "2_2") (pintype "passive"))
      (node (ref "L11") (pin "1") (pinfunction "1_1") (pintype "passive"))
      (node (ref "RN5") (pin "1") (pinfunction "1_1") (pintype "passive"))
    )
    (net (code "272") (name "~{RW_VRAM}") (class "Default")
      (node (ref "IC2") (pin "4") (pinfunction "~{WE}_4") (pintype "input"))
      (node (ref "IC3") (pin "4") (pinfunction "~{WE}_4") (pintype "input"))
      (node (ref "IC4") (pin "4") (pinfunction "~{WE}_4") (pintype "input"))
      (node (ref "IC5") (pin "4") (pinfunction "~{WE}_4") (pintype "input"))
      (node (ref "IC9") (pin "57") (pinfunction "R/~{W}_57") (pintype "bidirectional"))
    )
    (net (code "273") (name "~{SCE}") (class "Default")
      (node (ref "IC10") (pin "97") (pinfunction "PB8/4_97") (pintype "input"))
      (node (ref "IC6") (pin "8") (pinfunction "~{CE}_8") (pintype "bidirectional"))
    )
    (net (code "274") (name "~{SLOT_INT}") (class "Default")
      (node (ref "CN1") (pin "8") (pinfunction "8_8") (pintype "bidirectional"))
      (node (ref "CN2") (pin "8") (pinfunction "8_8") (pintype "bidirectional"))
      (node (ref "IC10") (pin "19") (pinfunction "PB1/5_19") (pintype "input"))
    )
    (net (code "275") (name "~{VDPR}") (class "Default")
      (node (ref "IC10") (pin "14") (pinfunction "PB2/16_14") (pintype "input"))
      (node (ref "IC9") (pin "31") (pinfunction "~{CSR}_31") (pintype "bidirectional"))
    )
    (net (code "276") (name "~{VDPW}") (class "Default")
      (node (ref "IC10") (pin "15") (pinfunction "PB2/17_15") (pintype "input"))
      (node (ref "IC9") (pin "30") (pinfunction "~{CSW}_30") (pintype "bidirectional"))
    )
    (net (code "277") (name "~{VDP_INT}") (class "Default")
      (node (ref "IC10") (pin "16") (pinfunction "PB1/2_16") (pintype "input"))
      (node (ref "IC9") (pin "25") (pinfunction "~{INT}_25") (pintype "bidirectional"))
      (node (ref "R15") (pin "1") (pinfunction "1_1") (pintype "passive"))
    )
    (net (code "278") (name "~{VRESET}") (class "Default")
      (node (ref "IC10") (pin "7") (pinfunction "PB2/10_7") (pintype "input"))
      (node (ref "IC9") (pin "4") (pinfunction "VRESET_4") (pintype "bidirectional"))
    )
  )
)
